# core_io5.net
KiCad netlist of a schematic drawn in EAGLE
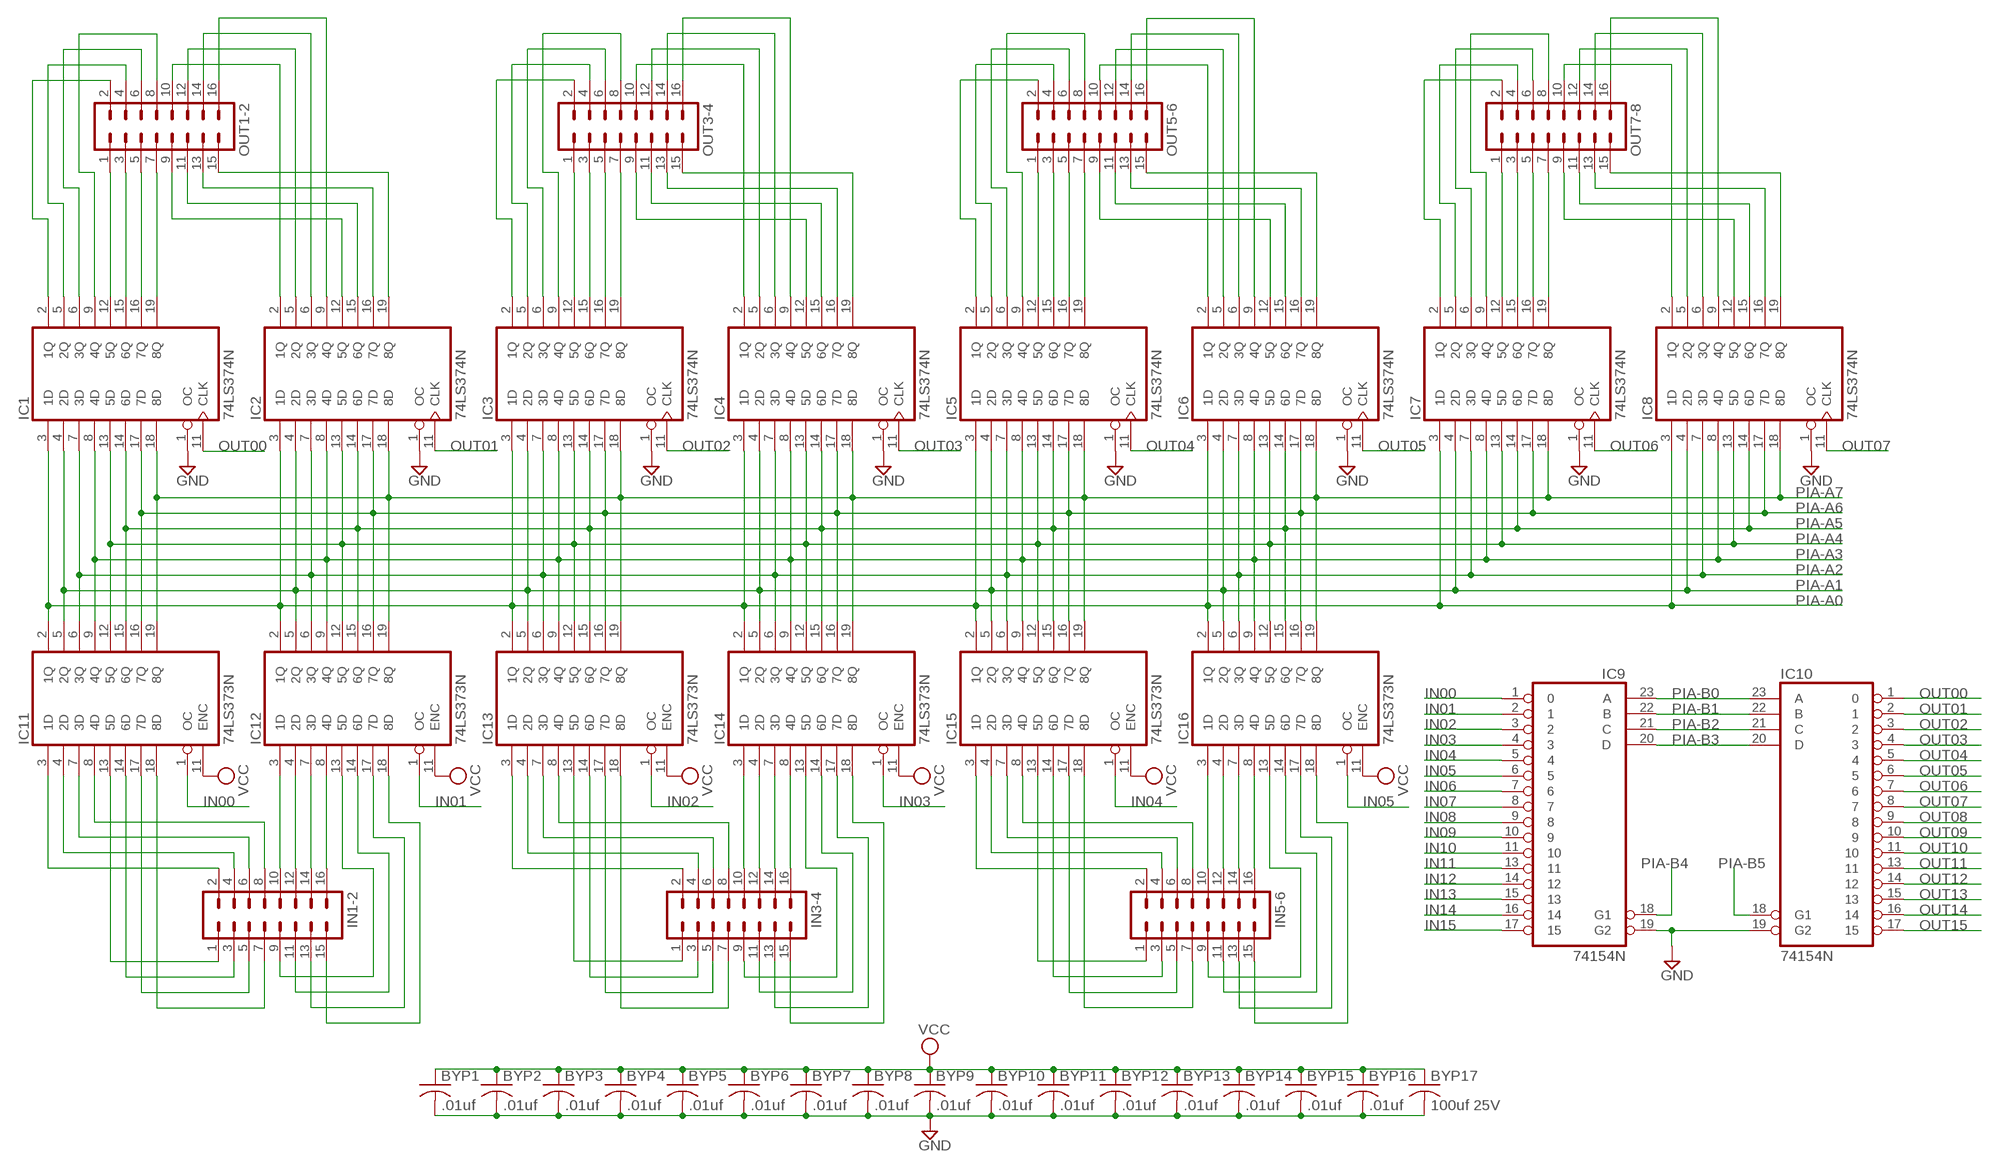
[diagram p0: schematic, sheet 1]
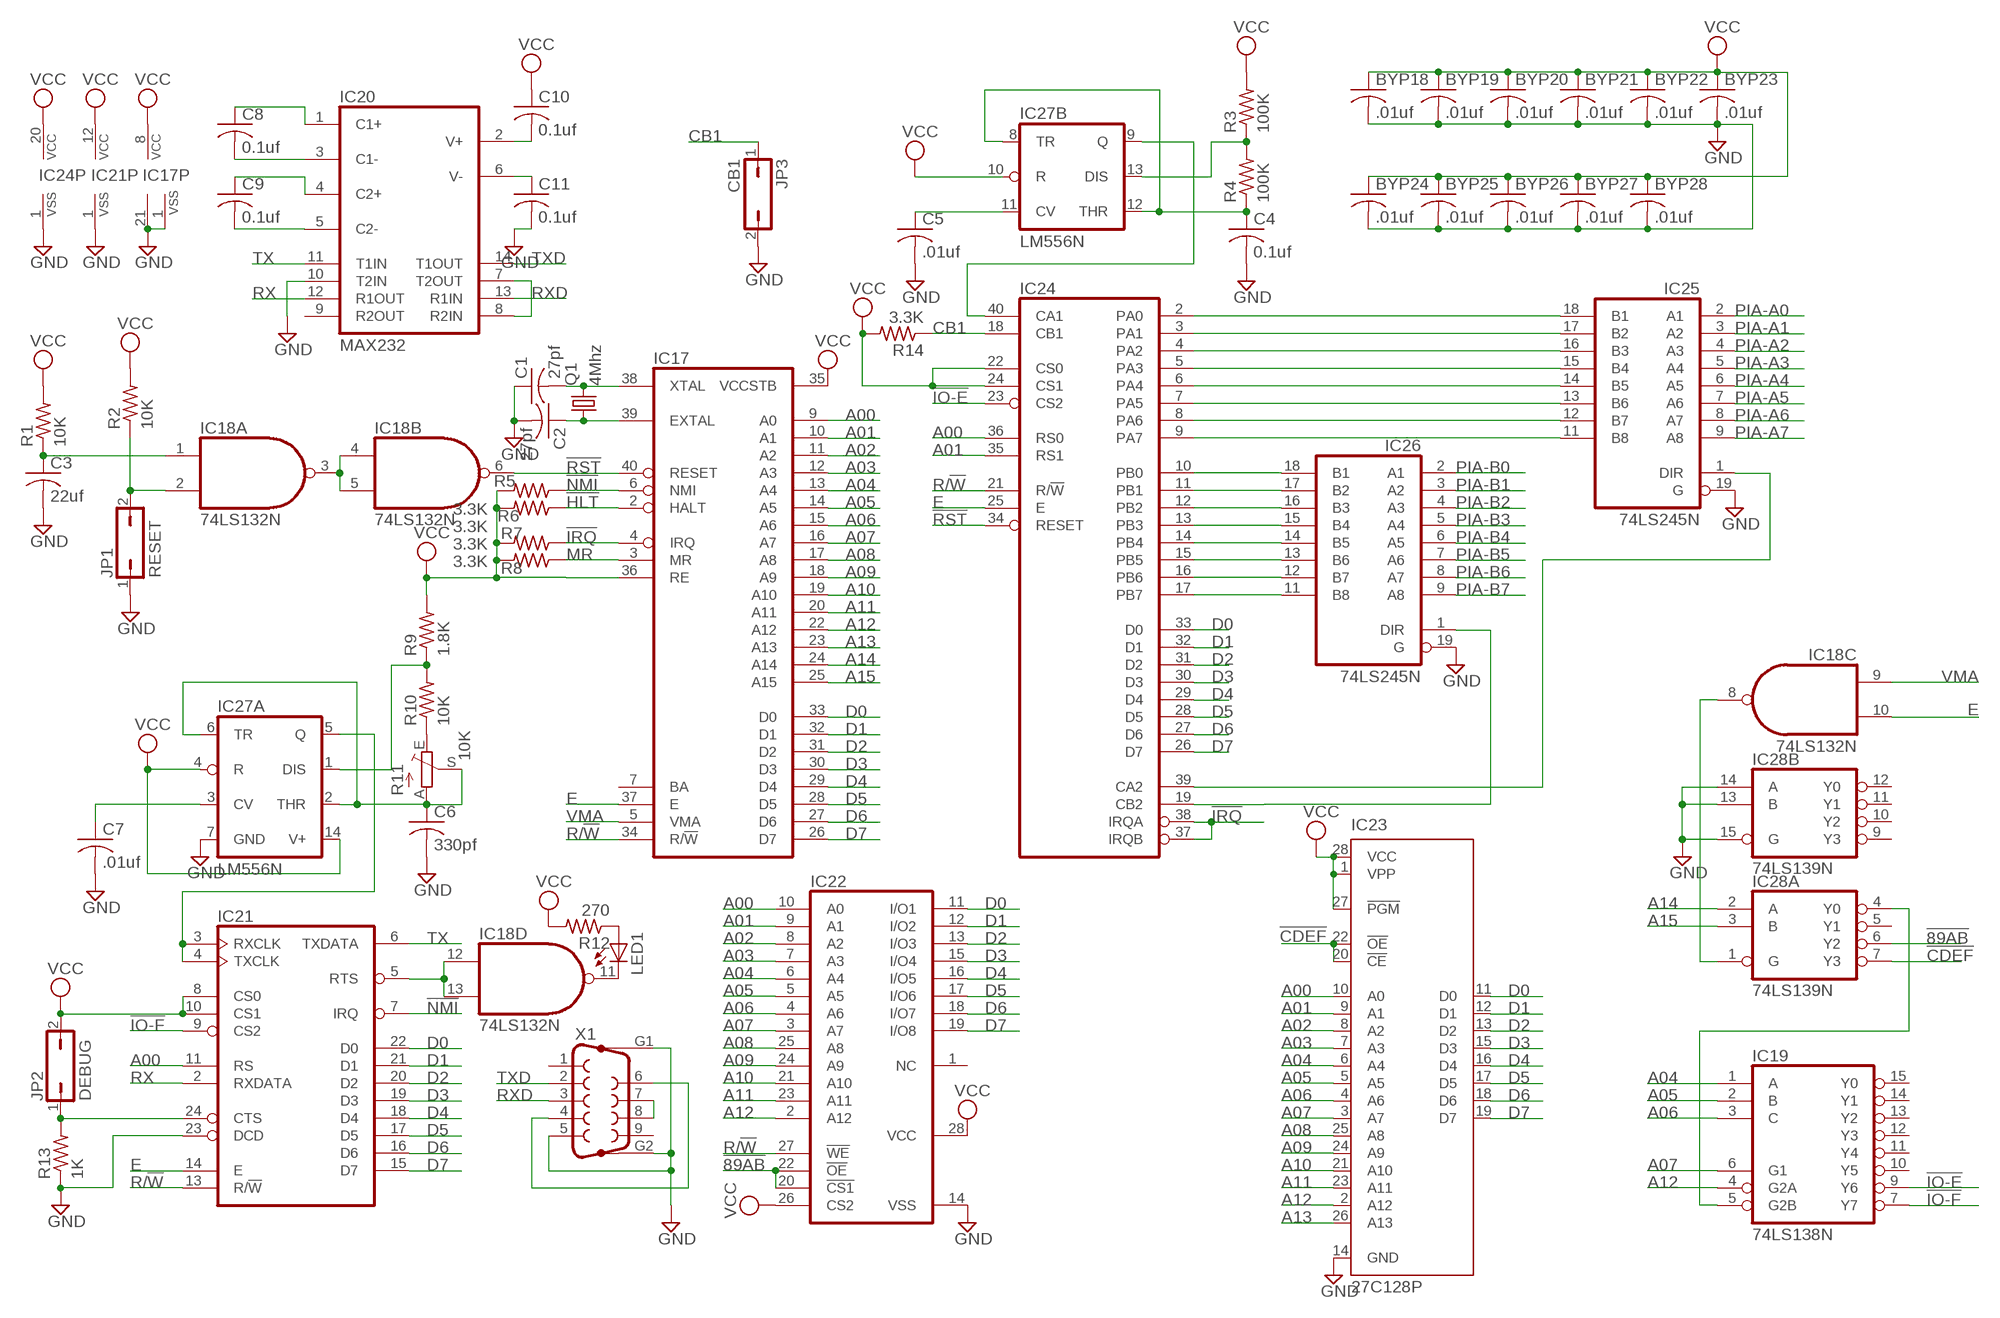
[diagram p1: schematic, sheet 2]
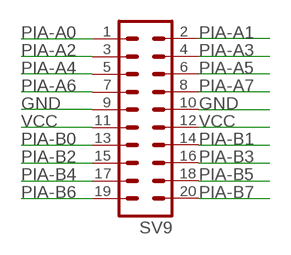
[diagram p2: schematic, sheet 3]

(export (version "E")
  (design (tool "Eeschema 10.0.6"))
  (components
    (comp (ref "BYP1")
      (value ".01uf")
      (footprint "eagle-import:C050-025X075")
      (libsource (lib "eagle-import") (part "C-US050-025X075"))
    )
    (comp (ref "BYP2")
      (value ".01uf")
      (footprint "eagle-import:C050-025X075")
      (libsource (lib "eagle-import") (part "C-US050-025X075"))
    )
    (comp (ref "BYP3")
      (value ".01uf")
      (footprint "eagle-import:C050-025X075")
      (libsource (lib "eagle-import") (part "C-US050-025X075"))
    )
    (comp (ref "BYP4")
      (value ".01uf")
      (footprint "eagle-import:C050-025X075")
      (libsource (lib "eagle-import") (part "C-US050-025X075"))
    )
    (comp (ref "BYP5")
      (value ".01uf")
      (footprint "eagle-import:C050-025X075")
      (libsource (lib "eagle-import") (part "C-US050-025X075"))
    )
    (comp (ref "BYP6")
      (value ".01uf")
      (footprint "eagle-import:C050-025X075")
      (libsource (lib "eagle-import") (part "C-US050-025X075"))
    )
    (comp (ref "BYP7")
      (value ".01uf")
      (footprint "eagle-import:C050-025X075")
      (libsource (lib "eagle-import") (part "C-US050-025X075"))
    )
    (comp (ref "BYP8")
      (value ".01uf")
      (footprint "eagle-import:C050-025X075")
      (libsource (lib "eagle-import") (part "C-US050-025X075"))
    )
    (comp (ref "BYP9")
      (value ".01uf")
      (footprint "eagle-import:C050-025X075")
      (libsource (lib "eagle-import") (part "C-US050-025X075"))
    )
    (comp (ref "BYP10")
      (value ".01uf")
      (footprint "eagle-import:C050-025X075")
      (libsource (lib "eagle-import") (part "C-US050-025X075"))
    )
    (comp (ref "BYP11")
      (value ".01uf")
      (footprint "eagle-import:C050-025X075")
      (libsource (lib "eagle-import") (part "C-US050-025X075"))
    )
    (comp (ref "BYP12")
      (value ".01uf")
      (footprint "eagle-import:C050-025X075")
      (libsource (lib "eagle-import") (part "C-US050-025X075"))
    )
    (comp (ref "BYP13")
      (value ".01uf")
      (footprint "eagle-import:C050-025X075")
      (libsource (lib "eagle-import") (part "C-US050-025X075"))
    )
    (comp (ref "BYP14")
      (value ".01uf")
      (footprint "eagle-import:C050-025X075")
      (libsource (lib "eagle-import") (part "C-US050-025X075"))
    )
    (comp (ref "BYP15")
      (value ".01uf")
      (footprint "eagle-import:C050-025X075")
      (libsource (lib "eagle-import") (part "C-US050-025X075"))
    )
    (comp (ref "BYP16")
      (value ".01uf")
      (footprint "eagle-import:C050-025X075")
      (libsource (lib "eagle-import") (part "C-US050-025X075"))
    )
    (comp (ref "BYP17")
      (value "100uf 25V")
      (footprint "eagle-import:C102-043X133")
      (libsource (lib "eagle-import") (part "C-US102-043X133"))
    )
    (comp (ref "IC1")
      (value "74LS374N")
      (footprint "eagle-import:DIL20")
      (libsource (lib "eagle-import") (part "74374NLS"))
    )
    (comp (ref "IC2")
      (value "74LS374N")
      (footprint "eagle-import:DIL20")
      (libsource (lib "eagle-import") (part "74374NLS"))
    )
    (comp (ref "IC3")
      (value "74LS374N")
      (footprint "eagle-import:DIL20")
      (libsource (lib "eagle-import") (part "74374NLS"))
    )
    (comp (ref "IC4")
      (value "74LS374N")
      (footprint "eagle-import:DIL20")
      (libsource (lib "eagle-import") (part "74374NLS"))
    )
    (comp (ref "IC5")
      (value "74LS374N")
      (footprint "eagle-import:DIL20")
      (libsource (lib "eagle-import") (part "74374NLS"))
    )
    (comp (ref "IC6")
      (value "74LS374N")
      (footprint "eagle-import:DIL20")
      (libsource (lib "eagle-import") (part "74374NLS"))
    )
    (comp (ref "IC7")
      (value "74LS374N")
      (footprint "eagle-import:DIL20")
      (libsource (lib "eagle-import") (part "74374NLS"))
    )
    (comp (ref "IC8")
      (value "74LS374N")
      (footprint "eagle-import:DIL20")
      (libsource (lib "eagle-import") (part "74374NLS"))
    )
    (comp (ref "IC9")
      (value "74154N")
      (footprint "eagle-import:DIL24-6")
      (libsource (lib "eagle-import") (part "74154N"))
    )
    (comp (ref "IC10")
      (value "74154N")
      (footprint "eagle-import:DIL24-6")
      (libsource (lib "eagle-import") (part "74154N"))
    )
    (comp (ref "IC11")
      (value "74LS373N")
      (footprint "eagle-import:DIL20")
      (libsource (lib "eagle-import") (part "74373NLS"))
    )
    (comp (ref "IC12")
      (value "74LS373N")
      (footprint "eagle-import:DIL20")
      (libsource (lib "eagle-import") (part "74373NLS"))
    )
    (comp (ref "IC13")
      (value "74LS373N")
      (footprint "eagle-import:DIL20")
      (libsource (lib "eagle-import") (part "74373NLS"))
    )
    (comp (ref "IC14")
      (value "74LS373N")
      (footprint "eagle-import:DIL20")
      (libsource (lib "eagle-import") (part "74373NLS"))
    )
    (comp (ref "IC15")
      (value "74LS373N")
      (footprint "eagle-import:DIL20")
      (libsource (lib "eagle-import") (part "74373NLS"))
    )
    (comp (ref "IC16")
      (value "74LS373N")
      (footprint "eagle-import:DIL20")
      (libsource (lib "eagle-import") (part "74373NLS"))
    )
    (comp (ref "IN1-2")
      (value "MA08-2")
      (footprint "eagle-import:MA08-2")
      (libsource (lib "eagle-import") (part "MA08-2"))
    )
    (comp (ref "IN3-4")
      (value "MA08-2")
      (footprint "eagle-import:MA08-2")
      (libsource (lib "eagle-import") (part "MA08-2"))
    )
    (comp (ref "IN5-6")
      (value "MA08-2")
      (footprint "eagle-import:MA08-2")
      (libsource (lib "eagle-import") (part "MA08-2"))
    )
    (comp (ref "OUT1-2")
      (value "MA08-2")
      (footprint "eagle-import:MA08-2")
      (libsource (lib "eagle-import") (part "MA08-2"))
    )
    (comp (ref "OUT3-4")
      (value "MA08-2")
      (footprint "eagle-import:MA08-2")
      (libsource (lib "eagle-import") (part "MA08-2"))
    )
    (comp (ref "OUT5-6")
      (value "MA08-2")
      (footprint "eagle-import:MA08-2")
      (libsource (lib "eagle-import") (part "MA08-2"))
    )
    (comp (ref "OUT7-8")
      (value "MA08-2")
      (footprint "eagle-import:MA08-2")
      (libsource (lib "eagle-import") (part "MA08-2"))
    )
    (comp (ref "BYP18")
      (value ".01uf")
      (footprint "eagle-import:C050-025X075")
      (libsource (lib "eagle-import") (part "C-US050-025X075"))
    )
    (comp (ref "BYP19")
      (value ".01uf")
      (footprint "eagle-import:C050-025X075")
      (libsource (lib "eagle-import") (part "C-US050-025X075"))
    )
    (comp (ref "BYP20")
      (value ".01uf")
      (footprint "eagle-import:C050-025X075")
      (libsource (lib "eagle-import") (part "C-US050-025X075"))
    )
    (comp (ref "BYP21")
      (value ".01uf")
      (footprint "eagle-import:C050-025X075")
      (libsource (lib "eagle-import") (part "C-US050-025X075"))
    )
    (comp (ref "BYP22")
      (value ".01uf")
      (footprint "eagle-import:C050-025X075")
      (libsource (lib "eagle-import") (part "C-US050-025X075"))
    )
    (comp (ref "BYP23")
      (value ".01uf")
      (footprint "eagle-import:C050-025X075")
      (libsource (lib "eagle-import") (part "C-US050-025X075"))
    )
    (comp (ref "BYP24")
      (value ".01uf")
      (footprint "eagle-import:C050-025X075")
      (libsource (lib "eagle-import") (part "C-US050-025X075"))
    )
    (comp (ref "BYP25")
      (value ".01uf")
      (footprint "eagle-import:C050-025X075")
      (libsource (lib "eagle-import") (part "C-US050-025X075"))
    )
    (comp (ref "BYP26")
      (value ".01uf")
      (footprint "eagle-import:C050-025X075")
      (libsource (lib "eagle-import") (part "C-US050-025X075"))
    )
    (comp (ref "BYP27")
      (value ".01uf")
      (footprint "eagle-import:C050-025X075")
      (libsource (lib "eagle-import") (part "C-US050-025X075"))
    )
    (comp (ref "BYP28")
      (value ".01uf")
      (footprint "eagle-import:C050-025X075")
      (libsource (lib "eagle-import") (part "C-US050-025X075"))
    )
    (comp (ref "C1")
      (value "27pf")
      (footprint "eagle-import:C050-025X075")
      (libsource (lib "eagle-import") (part "C-US050-025X075"))
    )
    (comp (ref "C2")
      (value "27pf")
      (footprint "eagle-import:C050-025X075")
      (libsource (lib "eagle-import") (part "C-US050-025X075"))
    )
    (comp (ref "C3")
      (value "22uf")
      (footprint "eagle-import:C102-043X133")
      (libsource (lib "eagle-import") (part "C-US102-043X133"))
    )
    (comp (ref "C4")
      (value "0.1uf")
      (footprint "eagle-import:C050-025X075")
      (libsource (lib "eagle-import") (part "C-US050-025X075"))
    )
    (comp (ref "C5")
      (value ".01uf")
      (footprint "eagle-import:C050-025X075")
      (libsource (lib "eagle-import") (part "C-US050-025X075"))
    )
    (comp (ref "C6")
      (value "330pf")
      (footprint "eagle-import:C050-025X075")
      (libsource (lib "eagle-import") (part "C-US050-025X075"))
    )
    (comp (ref "C7")
      (value ".01uf")
      (footprint "eagle-import:C050-025X075")
      (libsource (lib "eagle-import") (part "C-US050-025X075"))
    )
    (comp (ref "C8")
      (value "0.1uf")
      (footprint "eagle-import:C050-025X075")
      (libsource (lib "eagle-import") (part "C-US050-025X075"))
    )
    (comp (ref "C9")
      (value "0.1uf")
      (footprint "eagle-import:C050-025X075")
      (libsource (lib "eagle-import") (part "C-US050-025X075"))
    )
    (comp (ref "C10")
      (value "0.1uf")
      (footprint "eagle-import:C050-025X075")
      (libsource (lib "eagle-import") (part "C-US050-025X075"))
    )
    (comp (ref "C11")
      (value "0.1uf")
      (footprint "eagle-import:C050-025X075")
      (libsource (lib "eagle-import") (part "C-US050-025X075"))
    )
    (comp (ref "IC17")
      (value "6802")
      (footprint "eagle-import:DIL40")
      (libsource (lib "eagle-import") (part "6802"))
    )
    (comp (ref "IC18")
      (value "74LS132N")
      (footprint "eagle-import:DIL14")
      (libsource (lib "eagle-import") (part "7400NLS"))
    )
    (comp (ref "IC19")
      (value "74LS138N")
      (footprint "eagle-import:DIL16")
      (libsource (lib "eagle-import") (part "74138NLS"))
    )
    (comp (ref "IC20")
      (value "MAX232")
      (footprint "eagle-import:DIL16")
      (fields (field (name "MF") "MAXIM") (field (name "MPN") "MAX232ACPE+"))
      (libsource (lib "eagle-import") (part "MAX232"))
    )
    (comp (ref "IC21")
      (value "6850")
      (footprint "eagle-import:DIL24")
      (fields (field (name "MF") "NTE ELECTRONICS") (field (name "MPN") "NTE6850"))
      (libsource (lib "eagle-import") (part "6850"))
    )
    (comp (ref "IC22")
      (value "6264A")
      (footprint "eagle-import:DIL28-6")
      (libsource (lib "eagle-import") (part "6264A"))
    )
    (comp (ref "IC23")
      (value "27C128P")
      (footprint "eagle-import:DIL28-6")
      (libsource (lib "eagle-import") (part "27128PC"))
    )
    (comp (ref "IC24")
      (value "6821")
      (footprint "eagle-import:DIL40")
      (fields (field (name "MF") "NTE ELECTRONICS") (field (name "MPN") "NTE6821"))
      (libsource (lib "eagle-import") (part "6821"))
    )
    (comp (ref "IC25")
      (value "74LS245N")
      (footprint "eagle-import:DIL20")
      (libsource (lib "eagle-import") (part "74245NLS"))
    )
    (comp (ref "IC26")
      (value "74LS245N")
      (footprint "eagle-import:DIL20")
      (libsource (lib "eagle-import") (part "74245NLS"))
    )
    (comp (ref "IC27")
      (value "LM556N")
      (footprint "eagle-import:DIL14")
      (libsource (lib "eagle-import") (part "556NLM"))
    )
    (comp (ref "IC28")
      (value "74LS139N")
      (footprint "eagle-import:DIL16")
      (libsource (lib "eagle-import") (part "74139NLS"))
    )
    (comp (ref "JP1")
      (value "RESET")
      (footprint "eagle-import:JP1")
      (libsource (lib "eagle-import") (part "JP1Q"))
    )
    (comp (ref "JP2")
      (value "DEBUG")
      (footprint "eagle-import:JP1")
      (libsource (lib "eagle-import") (part "JP1Q"))
    )
    (comp (ref "JP3")
      (value "CB1")
      (footprint "eagle-import:JP1")
      (libsource (lib "eagle-import") (part "JP1Q"))
    )
    (comp (ref "LED1")
      (value "LED3MM")
      (footprint "eagle-import:LED3MM")
      (libsource (lib "eagle-import") (part "LED3MM"))
    )
    (comp (ref "Q1")
      (value "4Mhz")
      (footprint "eagle-import:HC18U-V")
      (libsource (lib "eagle-import") (part "CRYSTALHC18U-V"))
    )
    (comp (ref "R1")
      (value "10K")
      (footprint "eagle-import:0207_7")
      (libsource (lib "eagle-import") (part "R-US_0207/7"))
    )
    (comp (ref "R2")
      (value "10K")
      (footprint "eagle-import:0207_7")
      (libsource (lib "eagle-import") (part "R-US_0207/7"))
    )
    (comp (ref "R3")
      (value "100K")
      (footprint "eagle-import:0207_7")
      (libsource (lib "eagle-import") (part "R-US_0207/7"))
    )
    (comp (ref "R4")
      (value "100K")
      (footprint "eagle-import:0207_7")
      (libsource (lib "eagle-import") (part "R-US_0207/7"))
    )
    (comp (ref "R5")
      (value "3.3K")
      (footprint "eagle-import:0207_7")
      (libsource (lib "eagle-import") (part "R-US_0207/7"))
    )
    (comp (ref "R6")
      (value "3.3K")
      (footprint "eagle-import:0207_7")
      (libsource (lib "eagle-import") (part "R-US_0207/7"))
    )
    (comp (ref "R7")
      (value "3.3K")
      (footprint "eagle-import:0207_7")
      (libsource (lib "eagle-import") (part "R-US_0207/7"))
    )
    (comp (ref "R8")
      (value "3.3K")
      (footprint "eagle-import:0207_7")
      (libsource (lib "eagle-import") (part "R-US_0207/7"))
    )
    (comp (ref "R9")
      (value "1.8K")
      (footprint "eagle-import:0207_7")
      (libsource (lib "eagle-import") (part "R-US_0207/7"))
    )
    (comp (ref "R10")
      (value "10K")
      (footprint "eagle-import:0207_7")
      (libsource (lib "eagle-import") (part "R-US_0207/7"))
    )
    (comp (ref "R11")
      (value "10K")
      (footprint "eagle-import:SP19L")
      (libsource (lib "eagle-import") (part "TRIM_EU-B90P"))
    )
    (comp (ref "R12")
      (value "270")
      (footprint "eagle-import:0207_7")
      (libsource (lib "eagle-import") (part "R-US_0207/7"))
    )
    (comp (ref "R13")
      (value "1K")
      (footprint "eagle-import:0207_7")
      (libsource (lib "eagle-import") (part "R-US_0207/7"))
    )
    (comp (ref "R14")
      (value "3.3K")
      (footprint "eagle-import:0207_7")
      (libsource (lib "eagle-import") (part "R-US_0207/7"))
    )
    (comp (ref "X1")
      (value "F09HP")
      (footprint "eagle-import:F09HP")
      (libsource (lib "eagle-import") (part "F09HP"))
    )
    (comp (ref "SV9")
      (value "MA10-2")
      (footprint "eagle-import:MA10-2")
      (libsource (lib "eagle-import") (part "MA10-2"))
    )
  )
  (nets
    (net (code "1") (name "A00") (class "Default")
      (node (ref "IC17") (pin "9") (pinfunction "A0_9") (pintype "output"))
      (node (ref "IC21") (pin "11") (pinfunction "RS_11") (pintype "input"))
      (node (ref "IC22") (pin "10") (pinfunction "A0_10") (pintype "input"))
      (node (ref "IC23") (pin "10") (pinfunction "A0_10") (pintype "input"))
      (node (ref "IC24") (pin "36") (pinfunction "RS0_36") (pintype "input"))
    )
    (net (code "2") (name "A01") (class "Default")
      (node (ref "IC17") (pin "10") (pinfunction "A1_10") (pintype "output"))
      (node (ref "IC22") (pin "9") (pinfunction "A1_9") (pintype "input"))
      (node (ref "IC23") (pin "9") (pinfunction "A1_9") (pintype "input"))
      (node (ref "IC24") (pin "35") (pinfunction "RS1_35") (pintype "input"))
    )
    (net (code "3") (name "A02") (class "Default")
      (node (ref "IC17") (pin "11") (pinfunction "A2_11") (pintype "output"))
      (node (ref "IC22") (pin "8") (pinfunction "A2_8") (pintype "input"))
      (node (ref "IC23") (pin "8") (pinfunction "A2_8") (pintype "input"))
    )
    (net (code "4") (name "A03") (class "Default")
      (node (ref "IC17") (pin "12") (pinfunction "A3_12") (pintype "output"))
      (node (ref "IC22") (pin "7") (pinfunction "A3_7") (pintype "input"))
      (node (ref "IC23") (pin "7") (pinfunction "A3_7") (pintype "input"))
    )
    (net (code "5") (name "A04") (class "Default")
      (node (ref "IC17") (pin "13") (pinfunction "A4_13") (pintype "output"))
      (node (ref "IC19") (pin "1") (pinfunction "A_1") (pintype "input"))
      (node (ref "IC22") (pin "6") (pinfunction "A4_6") (pintype "input"))
      (node (ref "IC23") (pin "6") (pinfunction "A4_6") (pintype "input"))
    )
    (net (code "6") (name "A05") (class "Default")
      (node (ref "IC17") (pin "14") (pinfunction "A5_14") (pintype "output"))
      (node (ref "IC19") (pin "2") (pinfunction "B_2") (pintype "input"))
      (node (ref "IC22") (pin "5") (pinfunction "A5_5") (pintype "input"))
      (node (ref "IC23") (pin "5") (pinfunction "A5_5") (pintype "input"))
    )
    (net (code "7") (name "A06") (class "Default")
      (node (ref "IC17") (pin "15") (pinfunction "A6_15") (pintype "output"))
      (node (ref "IC19") (pin "3") (pinfunction "C_3") (pintype "input"))
      (node (ref "IC22") (pin "4") (pinfunction "A6_4") (pintype "input"))
      (node (ref "IC23") (pin "4") (pinfunction "A6_4") (pintype "input"))
    )
    (net (code "8") (name "A07") (class "Default")
      (node (ref "IC17") (pin "16") (pinfunction "A7_16") (pintype "output"))
      (node (ref "IC19") (pin "6") (pinfunction "G1_6") (pintype "input"))
      (node (ref "IC22") (pin "3") (pinfunction "A7_3") (pintype "input"))
      (node (ref "IC23") (pin "3") (pinfunction "A7_3") (pintype "input"))
    )
    (net (code "9") (name "A08") (class "Default")
      (node (ref "IC17") (pin "17") (pinfunction "A8_17") (pintype "output"))
      (node (ref "IC22") (pin "25") (pinfunction "A8_25") (pintype "input"))
      (node (ref "IC23") (pin "25") (pinfunction "A8_25") (pintype "input"))
    )
    (net (code "10") (name "A09") (class "Default")
      (node (ref "IC17") (pin "18") (pinfunction "A9_18") (pintype "output"))
      (node (ref "IC22") (pin "24") (pinfunction "A9_24") (pintype "input"))
      (node (ref "IC23") (pin "24") (pinfunction "A9_24") (pintype "input"))
    )
    (net (code "11") (name "A10") (class "Default")
      (node (ref "IC17") (pin "19") (pinfunction "A10_19") (pintype "output"))
      (node (ref "IC22") (pin "21") (pinfunction "A10_21") (pintype "input"))
      (node (ref "IC23") (pin "21") (pinfunction "A10_21") (pintype "input"))
    )
    (net (code "12") (name "A11") (class "Default")
      (node (ref "IC17") (pin "20") (pinfunction "A11_20") (pintype "output"))
      (node (ref "IC22") (pin "23") (pinfunction "A11_23") (pintype "input"))
      (node (ref "IC23") (pin "23") (pinfunction "A11_23") (pintype "input"))
    )
    (net (code "13") (name "A12") (class "Default")
      (node (ref "IC17") (pin "22") (pinfunction "A12_22") (pintype "output"))
      (node (ref "IC19") (pin "4") (pinfunction "G2A_4") (pintype "input"))
      (node (ref "IC22") (pin "2") (pinfunction "A12_2") (pintype "input"))
      (node (ref "IC23") (pin "2") (pinfunction "A12_2") (pintype "input"))
    )
    (net (code "14") (name "A13") (class "Default")
      (node (ref "IC17") (pin "23") (pinfunction "A13_23") (pintype "output"))
      (node (ref "IC23") (pin "26") (pinfunction "A13_26") (pintype "input"))
    )
    (net (code "15") (name "A14") (class "Default")
      (node (ref "IC17") (pin "24") (pinfunction "A14_24") (pintype "output"))
      (node (ref "IC28") (pin "2") (pinfunction "A_2") (pintype "input"))
    )
    (net (code "16") (name "A15") (class "Default")
      (node (ref "IC17") (pin "25") (pinfunction "A15_25") (pintype "output"))
      (node (ref "IC28") (pin "3") (pinfunction "B_3") (pintype "input"))
    )
    (net (code "17") (name "CB1") (class "Default")
      (node (ref "IC24") (pin "18") (pinfunction "CB1_18") (pintype "input"))
      (node (ref "JP3") (pin "1") (pinfunction "1_1") (pintype "passive"))
      (node (ref "R14") (pin "1") (pinfunction "1_1") (pintype "passive"))
    )
    (net (code "18") (name "D0") (class "Default")
      (node (ref "IC17") (pin "33") (pinfunction "D0_33") (pintype "bidirectional"))
      (node (ref "IC21") (pin "22") (pinfunction "D0_22") (pintype "bidirectional"))
      (node (ref "IC22") (pin "11") (pinfunction "I/O1_11") (pintype "bidirectional"))
      (node (ref "IC23") (pin "11") (pinfunction "D0_11") (pintype "tri_state"))
      (node (ref "IC24") (pin "33") (pinfunction "D0_33") (pintype "bidirectional"))
    )
    (net (code "19") (name "D1") (class "Default")
      (node (ref "IC17") (pin "32") (pinfunction "D1_32") (pintype "bidirectional"))
      (node (ref "IC21") (pin "21") (pinfunction "D1_21") (pintype "bidirectional"))
      (node (ref "IC22") (pin "12") (pinfunction "I/O2_12") (pintype "bidirectional"))
      (node (ref "IC23") (pin "12") (pinfunction "D1_12") (pintype "tri_state"))
      (node (ref "IC24") (pin "32") (pinfunction "D1_32") (pintype "bidirectional"))
    )
    (net (code "20") (name "D2") (class "Default")
      (node (ref "IC17") (pin "31") (pinfunction "D2_31") (pintype "bidirectional"))
      (node (ref "IC21") (pin "20") (pinfunction "D2_20") (pintype "bidirectional"))
      (node (ref "IC22") (pin "13") (pinfunction "I/O3_13") (pintype "bidirectional"))
      (node (ref "IC23") (pin "13") (pinfunction "D2_13") (pintype "tri_state"))
      (node (ref "IC24") (pin "31") (pinfunction "D2_31") (pintype "bidirectional"))
    )
    (net (code "21") (name "D3") (class "Default")
      (node (ref "IC17") (pin "30") (pinfunction "D3_30") (pintype "bidirectional"))
      (node (ref "IC21") (pin "19") (pinfunction "D3_19") (pintype "bidirectional"))
      (node (ref "IC22") (pin "15") (pinfunction "I/O4_15") (pintype "bidirectional"))
      (node (ref "IC23") (pin "15") (pinfunction "D3_15") (pintype "tri_state"))
      (node (ref "IC24") (pin "30") (pinfunction "D3_30") (pintype "bidirectional"))
    )
    (net (code "22") (name "D4") (class "Default")
      (node (ref "IC17") (pin "29") (pinfunction "D4_29") (pintype "bidirectional"))
      (node (ref "IC21") (pin "18") (pinfunction "D4_18") (pintype "bidirectional"))
      (node (ref "IC22") (pin "16") (pinfunction "I/O5_16") (pintype "bidirectional"))
      (node (ref "IC23") (pin "16") (pinfunction "D4_16") (pintype "tri_state"))
      (node (ref "IC24") (pin "29") (pinfunction "D4_29") (pintype "bidirectional"))
    )
    (net (code "23") (name "D5") (class "Default")
      (node (ref "IC17") (pin "28") (pinfunction "D5_28") (pintype "bidirectional"))
      (node (ref "IC21") (pin "17") (pinfunction "D5_17") (pintype "bidirectional"))
      (node (ref "IC22") (pin "17") (pinfunction "I/O6_17") (pintype "bidirectional"))
      (node (ref "IC23") (pin "17") (pinfunction "D5_17") (pintype "tri_state"))
      (node (ref "IC24") (pin "28") (pinfunction "D5_28") (pintype "bidirectional"))
    )
    (net (code "24") (name "D6") (class "Default")
      (node (ref "IC17") (pin "27") (pinfunction "D6_27") (pintype "bidirectional"))
      (node (ref "IC21") (pin "16") (pinfunction "D6_16") (pintype "bidirectional"))
      (node (ref "IC22") (pin "18") (pinfunction "I/O7_18") (pintype "bidirectional"))
      (node (ref "IC23") (pin "18") (pinfunction "D6_18") (pintype "tri_state"))
      (node (ref "IC24") (pin "27") (pinfunction "D6_27") (pintype "bidirectional"))
    )
    (net (code "25") (name "D7") (class "Default")
      (node (ref "IC17") (pin "26") (pinfunction "D7_26") (pintype "bidirectional"))
      (node (ref "IC21") (pin "15") (pinfunction "D7_15") (pintype "bidirectional"))
      (node (ref "IC22") (pin "19") (pinfunction "I/O8_19") (pintype "bidirectional"))
      (node (ref "IC23") (pin "19") (pinfunction "D7_19") (pintype "tri_state"))
      (node (ref "IC24") (pin "26") (pinfunction "D7_26") (pintype "bidirectional"))
    )
    (net (code "26") (name "E") (class "Default")
      (node (ref "IC17") (pin "37") (pinfunction "E_37") (pintype "output"))
      (node (ref "IC18") (pin "10") (pinfunction "I1_10") (pintype "input"))
      (node (ref "IC21") (pin "14") (pinfunction "E_14") (pintype "input"))
      (node (ref "IC24") (pin "25") (pinfunction "E_25") (pintype "input"))
    )
    (net (code "27") (name "GND") (class "Default")
      (node (ref "BYP1") (pin "2") (pinfunction "2_2") (pintype "passive"))
      (node (ref "BYP10") (pin "2") (pinfunction "2_2") (pintype "passive"))
      (node (ref "BYP11") (pin "2") (pinfunction "2_2") (pintype "passive"))
      (node (ref "BYP12") (pin "2") (pinfunction "2_2") (pintype "passive"))
      (node (ref "BYP13") (pin "2") (pinfunction "2_2") (pintype "passive"))
      (node (ref "BYP14") (pin "2") (pinfunction "2_2") (pintype "passive"))
      (node (ref "BYP15") (pin "2") (pinfunction "2_2") (pintype "passive"))
      (node (ref "BYP16") (pin "2") (pinfunction "2_2") (pintype "passive"))
      (node (ref "BYP17") (pin "2") (pinfunction "2_2") (pintype "passive"))
      (node (ref "BYP18") (pin "2") (pinfunction "2_2") (pintype "passive"))
      (node (ref "BYP19") (pin "2") (pinfunction "2_2") (pintype "passive"))
      (node (ref "BYP2") (pin "2") (pinfunction "2_2") (pintype "passive"))
      (node (ref "BYP20") (pin "2") (pinfunction "2_2") (pintype "passive"))
      (node (ref "BYP21") (pin "2") (pinfunction "2_2") (pintype "passive"))
      (node (ref "BYP22") (pin "2") (pinfunction "2_2") (pintype "passive"))
      (node (ref "BYP23") (pin "2") (pinfunction "2_2") (pintype "passive"))
      (node (ref "BYP24") (pin "2") (pinfunction "2_2") (pintype "passive"))
      (node (ref "BYP25") (pin "2") (pinfunction "2_2") (pintype "passive"))
      (node (ref "BYP26") (pin "2") (pinfunction "2_2") (pintype "passive"))
      (node (ref "BYP27") (pin "2") (pinfunction "2_2") (pintype "passive"))
      (node (ref "BYP28") (pin "2") (pinfunction "2_2") (pintype "passive"))
      (node (ref "BYP3") (pin "2") (pinfunction "2_2") (pintype "passive"))
      (node (ref "BYP4") (pin "2") (pinfunction "2_2") (pintype "passive"))
      (node (ref "BYP5") (pin "2") (pinfunction "2_2") (pintype "passive"))
      (node (ref "BYP6") (pin "2") (pinfunction "2_2") (pintype "passive"))
      (node (ref "BYP7") (pin "2") (pinfunction "2_2") (pintype "passive"))
      (node (ref "BYP8") (pin "2") (pinfunction "2_2") (pintype "passive"))
      (node (ref "BYP9") (pin "2") (pinfunction "2_2") (pintype "passive"))
      (node (ref "C1") (pin "1") (pinfunction "1_1") (pintype "passive"))
      (node (ref "C11") (pin "2") (pinfunction "2_2") (pintype "passive"))
      (node (ref "C2") (pin "2") (pinfunction "2_2") (pintype "passive"))
      (node (ref "C3") (pin "2") (pinfunction "2_2") (pintype "passive"))
      (node (ref "C4") (pin "2") (pinfunction "2_2") (pintype "passive"))
      (node (ref "C5") (pin "2") (pinfunction "2_2") (pintype "passive"))
      (node (ref "C6") (pin "2") (pinfunction "2_2") (pintype "passive"))
      (node (ref "C7") (pin "2") (pinfunction "2_2") (pintype "passive"))
      (node (ref "IC1") (pin "1") (pinfunction "OC_1") (pintype "input"))
      (node (ref "IC10") (pin "19") (pinfunction "G2_19") (pintype "input"))
      (node (ref "IC17") (pin "1") (pinfunction "VSS_1") (pintype "power_in"))
      (node (ref "IC17") (pin "21") (pinfunction "VSS_21") (pintype "power_in"))
      (node (ref "IC2") (pin "1") (pinfunction "OC_1") (pintype "input"))
      (node (ref "IC20") (pin "10") (pinfunction "T2IN_10") (pintype "input"))
      (node (ref "IC21") (pin "1") (pinfunction "VSS_1") (pintype "power_in"))
      (node (ref "IC21") (pin "23") (pinfunction "DCD_23") (pintype "input"))
      (node (ref "IC22") (pin "14") (pinfunction "VSS_14") (pintype "power_in"))
      (node (ref "IC23") (pin "14") (pinfunction "GND_14") (pintype "power_in"))
      (node (ref "IC24") (pin "1") (pinfunction "VSS_1") (pintype "power_in"))
      (node (ref "IC25") (pin "19") (pinfunction "G_19") (pintype "input"))
      (node (ref "IC26") (pin "19") (pinfunction "G_19") (pintype "input"))
      (node (ref "IC27") (pin "7") (pinfunction "GND_7") (pintype "power_in"))
      (node (ref "IC28") (pin "13") (pinfunction "B_13") (pintype "input"))
      (node (ref "IC28") (pin "14") (pinfunction "A_14") (pintype "input"))
      (node (ref "IC28") (pin "15") (pinfunction "G_15") (pintype "input"))
      (node (ref "IC3") (pin "1") (pinfunction "OC_1") (pintype "input"))
      (node (ref "IC4") (pin "1") (pinfunction "OC_1") (pintype "input"))
      (node (ref "IC5") (pin "1") (pinfunction "OC_1") (pintype "input"))
      (node (ref "IC6") (pin "1") (pinfunction "OC_1") (pintype "input"))
      (node (ref "IC7") (pin "1") (pinfunction "OC_1") (pintype "input"))
      (node (ref "IC8") (pin "1") (pinfunction "OC_1") (pintype "input"))
      (node (ref "IC9") (pin "19") (pinfunction "G2_19") (pintype "input"))
      (node (ref "JP1") (pin "1") (pinfunction "1_1") (pintype "passive"))
      (node (ref "JP3") (pin "2") (pinfunction "2_2") (pintype "passive"))
      (node (ref "R13") (pin "1") (pinfunction "1_1") (pintype "passive"))
      (node (ref "SV9") (pin "10") (pinfunction "10_10") (pintype "passive"))
      (node (ref "SV9") (pin "9") (pinfunction "9_9") (pintype "passive"))
      (node (ref "X1") (pin "5") (pinfunction "5_5") (pintype "passive"))
      (node (ref "X1") (pin "G1") (pinfunction "G1_G1") (pintype "passive"))
      (node (ref "X1") (pin "G2") (pinfunction "G2_G2") (pintype "passive"))
    )
    (net (code "28") (name "IN00") (class "Default")
      (node (ref "IC11") (pin "1") (pinfunction "OC_1") (pintype "input"))
      (node (ref "IC9") (pin "1") (pinfunction "0_1") (pintype "output"))
    )
    (net (code "29") (name "IN01") (class "Default")
      (node (ref "IC12") (pin "1") (pinfunction "OC_1") (pintype "input"))
      (node (ref "IC9") (pin "2") (pinfunction "1_2") (pintype "output"))
    )
    (net (code "30") (name "IN02") (class "Default")
      (node (ref "IC13") (pin "1") (pinfunction "OC_1") (pintype "input"))
      (node (ref "IC9") (pin "3") (pinfunction "2_3") (pintype "output"))
    )
    (net (code "31") (name "IN03") (class "Default")
      (node (ref "IC14") (pin "1") (pinfunction "OC_1") (pintype "input"))
      (node (ref "IC9") (pin "4") (pinfunction "3_4") (pintype "output"))
    )
    (net (code "32") (name "IN04") (class "Default")
      (node (ref "IC15") (pin "1") (pinfunction "OC_1") (pintype "input"))
      (node (ref "IC9") (pin "5") (pinfunction "4_5") (pintype "output"))
    )
    (net (code "33") (name "IN05") (class "Default")
      (node (ref "IC16") (pin "1") (pinfunction "OC_1") (pintype "input"))
      (node (ref "IC9") (pin "6") (pinfunction "5_6") (pintype "output"))
    )
    (net (code "34") (name "IN06") (class "Default")
      (node (ref "IC9") (pin "7") (pinfunction "6_7") (pintype "output"))
    )
    (net (code "35") (name "IN07") (class "Default")
      (node (ref "IC9") (pin "8") (pinfunction "7_8") (pintype "output"))
    )
    (net (code "36") (name "IN08") (class "Default")
      (node (ref "IC9") (pin "9") (pinfunction "8_9") (pintype "output"))
    )
    (net (code "37") (name "IN09") (class "Default")
      (node (ref "IC9") (pin "10") (pinfunction "9_10") (pintype "output"))
    )
    (net (code "38") (name "IN10") (class "Default")
      (node (ref "IC9") (pin "11") (pinfunction "10_11") (pintype "output"))
    )
    (net (code "39") (name "IN11") (class "Default")
      (node (ref "IC9") (pin "13") (pinfunction "11_13") (pintype "output"))
    )
    (net (code "40") (name "IN12") (class "Default")
      (node (ref "IC9") (pin "14") (pinfunction "12_14") (pintype "output"))
    )
    (net (code "41") (name "IN13") (class "Default")
      (node (ref "IC9") (pin "15") (pinfunction "13_15") (pintype "output"))
    )
    (net (code "42") (name "IN14") (class "Default")
      (node (ref "IC9") (pin "16") (pinfunction "14_16") (pintype "output"))
    )
    (net (code "43") (name "IN15") (class "Default")
      (node (ref "IC9") (pin "17") (pinfunction "15_17") (pintype "output"))
    )
    (net (code "44") (name "MR") (class "Default")
      (node (ref "IC17") (pin "3") (pinfunction "MR_3") (pintype "input"))
      (node (ref "R8") (pin "1") (pinfunction "1_1") (pintype "passive"))
    )
    (net (code "45") (name "Net-(IC1A-1Q)") (class "Default")
      (node (ref "IC1") (pin "2") (pinfunction "1Q_2") (pintype "tri_state"))
      (node (ref "OUT1-2") (pin "2") (pinfunction "2_2") (pintype "passive"))
    )
    (net (code "46") (name "Net-(IC1A-2Q)") (class "Default")
      (node (ref "IC1") (pin "5") (pinfunction "2Q_5") (pintype "tri_state"))
      (node (ref "OUT1-2") (pin "4") (pinfunction "4_4") (pintype "passive"))
    )
    (net (code "47") (name "Net-(IC1A-3Q)") (class "Default")
      (node (ref "IC1") (pin "6") (pinfunction "3Q_6") (pintype "tri_state"))
      (node (ref "OUT1-2") (pin "6") (pinfunction "6_6") (pintype "passive"))
    )
    (net (code "48") (name "Net-(IC1A-4Q)") (class "Default")
      (node (ref "IC1") (pin "9") (pinfunction "4Q_9") (pintype "tri_state"))
      (node (ref "OUT1-2") (pin "8") (pinfunction "8_8") (pintype "passive"))
    )
    (net (code "49") (name "Net-(IC1A-5Q)") (class "Default")
      (node (ref "IC1") (pin "12") (pinfunction "5Q_12") (pintype "tri_state"))
      (node (ref "OUT1-2") (pin "1") (pinfunction "1_1") (pintype "passive"))
    )
    (net (code "50") (name "Net-(IC1A-6Q)") (class "Default")
      (node (ref "IC1") (pin "15") (pinfunction "6Q_15") (pintype "tri_state"))
      (node (ref "OUT1-2") (pin "3") (pinfunction "3_3") (pintype "passive"))
    )
    (net (code "51") (name "Net-(IC1A-7Q)") (class "Default")
      (node (ref "IC1") (pin "16") (pinfunction "7Q_16") (pintype "tri_state"))
      (node (ref "OUT1-2") (pin "5") (pinfunction "5_5") (pintype "passive"))
    )
    (net (code "52") (name "Net-(IC1A-8Q)") (class "Default")
      (node (ref "IC1") (pin "19") (pinfunction "8Q_19") (pintype "tri_state"))
      (node (ref "OUT1-2") (pin "7") (pinfunction "7_7") (pintype "passive"))
    )
    (net (code "53") (name "Net-(IC2A-1Q)") (class "Default")
      (node (ref "IC2") (pin "2") (pinfunction "1Q_2") (pintype "tri_state"))
      (node (ref "OUT1-2") (pin "10") (pinfunction "10_10") (pintype "passive"))
    )
    (net (code "54") (name "Net-(IC2A-2Q)") (class "Default")
      (node (ref "IC2") (pin "5") (pinfunction "2Q_5") (pintype "tri_state"))
      (node (ref "OUT1-2") (pin "12") (pinfunction "12_12") (pintype "passive"))
    )
    (net (code "55") (name "Net-(IC2A-3Q)") (class "Default")
      (node (ref "IC2") (pin "6") (pinfunction "3Q_6") (pintype "tri_state"))
      (node (ref "OUT1-2") (pin "14") (pinfunction "14_14") (pintype "passive"))
    )
    (net (code "56") (name "Net-(IC2A-4Q)") (class "Default")
      (node (ref "IC2") (pin "9") (pinfunction "4Q_9") (pintype "tri_state"))
      (node (ref "OUT1-2") (pin "16") (pinfunction "16_16") (pintype "passive"))
    )
    (net (code "57") (name "Net-(IC2A-5Q)") (class "Default")
      (node (ref "IC2") (pin "12") (pinfunction "5Q_12") (pintype "tri_state"))
      (node (ref "OUT1-2") (pin "9") (pinfunction "9_9") (pintype "passive"))
    )
    (net (code "58") (name "Net-(IC2A-6Q)") (class "Default")
      (node (ref "IC2") (pin "15") (pinfunction "6Q_15") (pintype "tri_state"))
      (node (ref "OUT1-2") (pin "11") (pinfunction "11_11") (pintype "passive"))
    )
    (net (code "59") (name "Net-(IC2A-7Q)") (class "Default")
      (node (ref "IC2") (pin "16") (pinfunction "7Q_16") (pintype "tri_state"))
      (node (ref "OUT1-2") (pin "13") (pinfunction "13_13") (pintype "passive"))
    )
    (net (code "60") (name "Net-(IC2A-8Q)") (class "Default")
      (node (ref "IC2") (pin "19") (pinfunction "8Q_19") (pintype "tri_state"))
      (node (ref "OUT1-2") (pin "15") (pinfunction "15_15") (pintype "passive"))
    )
    (net (code "61") (name "Net-(IC3A-1Q)") (class "Default")
      (node (ref "IC3") (pin "2") (pinfunction "1Q_2") (pintype "tri_state"))
      (node (ref "OUT3-4") (pin "2") (pinfunction "2_2") (pintype "passive"))
    )
    (net (code "62") (name "Net-(IC3A-2Q)") (class "Default")
      (node (ref "IC3") (pin "5") (pinfunction "2Q_5") (pintype "tri_state"))
      (node (ref "OUT3-4") (pin "4") (pinfunction "4_4") (pintype "passive"))
    )
    (net (code "63") (name "Net-(IC3A-3Q)") (class "Default")
      (node (ref "IC3") (pin "6") (pinfunction "3Q_6") (pintype "tri_state"))
      (node (ref "OUT3-4") (pin "6") (pinfunction "6_6") (pintype "passive"))
    )
    (net (code "64") (name "Net-(IC3A-4Q)") (class "Default")
      (node (ref "IC3") (pin "9") (pinfunction "4Q_9") (pintype "tri_state"))
      (node (ref "OUT3-4") (pin "8") (pinfunction "8_8") (pintype "passive"))
    )
    (net (code "65") (name "Net-(IC3A-5Q)") (class "Default")
      (node (ref "IC3") (pin "12") (pinfunction "5Q_12") (pintype "tri_state"))
      (node (ref "OUT3-4") (pin "1") (pinfunction "1_1") (pintype "passive"))
    )
    (net (code "66") (name "Net-(IC3A-6Q)") (class "Default")
      (node (ref "IC3") (pin "15") (pinfunction "6Q_15") (pintype "tri_state"))
      (node (ref "OUT3-4") (pin "3") (pinfunction "3_3") (pintype "passive"))
    )
    (net (code "67") (name "Net-(IC3A-7Q)") (class "Default")
      (node (ref "IC3") (pin "16") (pinfunction "7Q_16") (pintype "tri_state"))
      (node (ref "OUT3-4") (pin "5") (pinfunction "5_5") (pintype "passive"))
    )
    (net (code "68") (name "Net-(IC3A-8Q)") (class "Default")
      (node (ref "IC3") (pin "19") (pinfunction "8Q_19") (pintype "tri_state"))
      (node (ref "OUT3-4") (pin "7") (pinfunction "7_7") (pintype "passive"))
    )
    (net (code "69") (name "Net-(IC4A-1Q)") (class "Default")
      (node (ref "IC4") (pin "2") (pinfunction "1Q_2") (pintype "tri_state"))
      (node (ref "OUT3-4") (pin "10") (pinfunction "10_10") (pintype "passive"))
    )
    (net (code "70") (name "Net-(IC4A-2Q)") (class "Default")
      (node (ref "IC4") (pin "5") (pinfunction "2Q_5") (pintype "tri_state"))
      (node (ref "OUT3-4") (pin "12") (pinfunction "12_12") (pintype "passive"))
    )
    (net (code "71") (name "Net-(IC4A-3Q)") (class "Default")
      (node (ref "IC4") (pin "6") (pinfunction "3Q_6") (pintype "tri_state"))
      (node (ref "OUT3-4") (pin "14") (pinfunction "14_14") (pintype "passive"))
    )
    (net (code "72") (name "Net-(IC4A-4Q)") (class "Default")
      (node (ref "IC4") (pin "9") (pinfunction "4Q_9") (pintype "tri_state"))
      (node (ref "OUT3-4") (pin "16") (pinfunction "16_16") (pintype "passive"))
    )
    (net (code "73") (name "Net-(IC4A-5Q)") (class "Default")
      (node (ref "IC4") (pin "12") (pinfunction "5Q_12") (pintype "tri_state"))
      (node (ref "OUT3-4") (pin "9") (pinfunction "9_9") (pintype "passive"))
    )
    (net (code "74") (name "Net-(IC4A-6Q)") (class "Default")
      (node (ref "IC4") (pin "15") (pinfunction "6Q_15") (pintype "tri_state"))
      (node (ref "OUT3-4") (pin "11") (pinfunction "11_11") (pintype "passive"))
    )
    (net (code "75") (name "Net-(IC4A-7Q)") (class "Default")
      (node (ref "IC4") (pin "16") (pinfunction "7Q_16") (pintype "tri_state"))
      (node (ref "OUT3-4") (pin "13") (pinfunction "13_13") (pintype "passive"))
    )
    (net (code "76") (name "Net-(IC4A-8Q)") (class "Default")
      (node (ref "IC4") (pin "19") (pinfunction "8Q_19") (pintype "tri_state"))
      (node (ref "OUT3-4") (pin "15") (pinfunction "15_15") (pintype "passive"))
    )
    (net (code "77") (name "Net-(IC5A-1Q)") (class "Default")
      (node (ref "IC5") (pin "2") (pinfunction "1Q_2") (pintype "tri_state"))
      (node (ref "OUT5-6") (pin "2") (pinfunction "2_2") (pintype "passive"))
    )
    (net (code "78") (name "Net-(IC5A-2Q)") (class "Default")
      (node (ref "IC5") (pin "5") (pinfunction "2Q_5") (pintype "tri_state"))
      (node (ref "OUT5-6") (pin "4") (pinfunction "4_4") (pintype "passive"))
    )
    (net (code "79") (name "Net-(IC5A-3Q)") (class "Default")
      (node (ref "IC5") (pin "6") (pinfunction "3Q_6") (pintype "tri_state"))
      (node (ref "OUT5-6") (pin "6") (pinfunction "6_6") (pintype "passive"))
    )
    (net (code "80") (name "Net-(IC5A-4Q)") (class "Default")
      (node (ref "IC5") (pin "9") (pinfunction "4Q_9") (pintype "tri_state"))
      (node (ref "OUT5-6") (pin "8") (pinfunction "8_8") (pintype "passive"))
    )
    (net (code "81") (name "Net-(IC5A-5Q)") (class "Default")
      (node (ref "IC5") (pin "12") (pinfunction "5Q_12") (pintype "tri_state"))
      (node (ref "OUT5-6") (pin "1") (pinfunction "1_1") (pintype "passive"))
    )
    (net (code "82") (name "Net-(IC5A-6Q)") (class "Default")
      (node (ref "IC5") (pin "15") (pinfunction "6Q_15") (pintype "tri_state"))
      (node (ref "OUT5-6") (pin "3") (pinfunction "3_3") (pintype "passive"))
    )
    (net (code "83") (name "Net-(IC5A-7Q)") (class "Default")
      (node (ref "IC5") (pin "16") (pinfunction "7Q_16") (pintype "tri_state"))
      (node (ref "OUT5-6") (pin "5") (pinfunction "5_5") (pintype "passive"))
    )
    (net (code "84") (name "Net-(IC5A-8Q)") (class "Default")
      (node (ref "IC5") (pin "19") (pinfunction "8Q_19") (pintype "tri_state"))
      (node (ref "OUT5-6") (pin "7") (pinfunction "7_7") (pintype "passive"))
    )
    (net (code "85") (name "Net-(IC6A-1Q)") (class "Default")
      (node (ref "IC6") (pin "2") (pinfunction "1Q_2") (pintype "tri_state"))
      (node (ref "OUT5-6") (pin "10") (pinfunction "10_10") (pintype "passive"))
    )
    (net (code "86") (name "Net-(IC6A-2Q)") (class "Default")
      (node (ref "IC6") (pin "5") (pinfunction "2Q_5") (pintype "tri_state"))
      (node (ref "OUT5-6") (pin "12") (pinfunction "12_12") (pintype "passive"))
    )
    (net (code "87") (name "Net-(IC6A-3Q)") (class "Default")
      (node (ref "IC6") (pin "6") (pinfunction "3Q_6") (pintype "tri_state"))
      (node (ref "OUT5-6") (pin "14") (pinfunction "14_14") (pintype "passive"))
    )
    (net (code "88") (name "Net-(IC6A-4Q)") (class "Default")
      (node (ref "IC6") (pin "9") (pinfunction "4Q_9") (pintype "tri_state"))
      (node (ref "OUT5-6") (pin "16") (pinfunction "16_16") (pintype "passive"))
    )
    (net (code "89") (name "Net-(IC6A-5Q)") (class "Default")
      (node (ref "IC6") (pin "12") (pinfunction "5Q_12") (pintype "tri_state"))
      (node (ref "OUT5-6") (pin "9") (pinfunction "9_9") (pintype "passive"))
    )
    (net (code "90") (name "Net-(IC6A-6Q)") (class "Default")
      (node (ref "IC6") (pin "15") (pinfunction "6Q_15") (pintype "tri_state"))
      (node (ref "OUT5-6") (pin "11") (pinfunction "11_11") (pintype "passive"))
    )
    (net (code "91") (name "Net-(IC6A-7Q)") (class "Default")
      (node (ref "IC6") (pin "16") (pinfunction "7Q_16") (pintype "tri_state"))
      (node (ref "OUT5-6") (pin "13") (pinfunction "13_13") (pintype "passive"))
    )
    (net (code "92") (name "Net-(IC6A-8Q)") (class "Default")
      (node (ref "IC6") (pin "19") (pinfunction "8Q_19") (pintype "tri_state"))
      (node (ref "OUT5-6") (pin "15") (pinfunction "15_15") (pintype "passive"))
    )
    (net (code "93") (name "Net-(IC7A-1Q)") (class "Default")
      (node (ref "IC7") (pin "2") (pinfunction "1Q_2") (pintype "tri_state"))
      (node (ref "OUT7-8") (pin "2") (pinfunction "2_2") (pintype "passive"))
    )
    (net (code "94") (name "Net-(IC7A-2Q)") (class "Default")
      (node (ref "IC7") (pin "5") (pinfunction "2Q_5") (pintype "tri_state"))
      (node (ref "OUT7-8") (pin "4") (pinfunction "4_4") (pintype "passive"))
    )
    (net (code "95") (name "Net-(IC7A-3Q)") (class "Default")
      (node (ref "IC7") (pin "6") (pinfunction "3Q_6") (pintype "tri_state"))
      (node (ref "OUT7-8") (pin "6") (pinfunction "6_6") (pintype "passive"))
    )
    (net (code "96") (name "Net-(IC7A-4Q)") (class "Default")
      (node (ref "IC7") (pin "9") (pinfunction "4Q_9") (pintype "tri_state"))
      (node (ref "OUT7-8") (pin "8") (pinfunction "8_8") (pintype "passive"))
    )
    (net (code "97") (name "Net-(IC7A-5Q)") (class "Default")
      (node (ref "IC7") (pin "12") (pinfunction "5Q_12") (pintype "tri_state"))
      (node (ref "OUT7-8") (pin "1") (pinfunction "1_1") (pintype "passive"))
    )
    (net (code "98") (name "Net-(IC7A-6Q)") (class "Default")
      (node (ref "IC7") (pin "15") (pinfunction "6Q_15") (pintype "tri_state"))
      (node (ref "OUT7-8") (pin "3") (pinfunction "3_3") (pintype "passive"))
    )
    (net (code "99") (name "Net-(IC7A-7Q)") (class "Default")
      (node (ref "IC7") (pin "16") (pinfunction "7Q_16") (pintype "tri_state"))
      (node (ref "OUT7-8") (pin "5") (pinfunction "5_5") (pintype "passive"))
    )
    (net (code "100") (name "Net-(IC7A-8Q)") (class "Default")
      (node (ref "IC7") (pin "19") (pinfunction "8Q_19") (pintype "tri_state"))
      (node (ref "OUT7-8") (pin "7") (pinfunction "7_7") (pintype "passive"))
    )
    (net (code "101") (name "Net-(IC8A-1Q)") (class "Default")
      (node (ref "IC8") (pin "2") (pinfunction "1Q_2") (pintype "tri_state"))
      (node (ref "OUT7-8") (pin "10") (pinfunction "10_10") (pintype "passive"))
    )
    (net (code "102") (name "Net-(IC8A-2Q)") (class "Default")
      (node (ref "IC8") (pin "5") (pinfunction "2Q_5") (pintype "tri_state"))
      (node (ref "OUT7-8") (pin "12") (pinfunction "12_12") (pintype "passive"))
    )
    (net (code "103") (name "Net-(IC8A-3Q)") (class "Default")
      (node (ref "IC8") (pin "6") (pinfunction "3Q_6") (pintype "tri_state"))
      (node (ref "OUT7-8") (pin "14") (pinfunction "14_14") (pintype "passive"))
    )
    (net (code "104") (name "Net-(IC8A-4Q)") (class "Default")
      (node (ref "IC8") (pin "9") (pinfunction "4Q_9") (pintype "tri_state"))
      (node (ref "OUT7-8") (pin "16") (pinfunction "16_16") (pintype "passive"))
    )
    (net (code "105") (name "Net-(IC8A-5Q)") (class "Default")
      (node (ref "IC8") (pin "12") (pinfunction "5Q_12") (pintype "tri_state"))
      (node (ref "OUT7-8") (pin "9") (pinfunction "9_9") (pintype "passive"))
    )
    (net (code "106") (name "Net-(IC8A-6Q)") (class "Default")
      (node (ref "IC8") (pin "15") (pinfunction "6Q_15") (pintype "tri_state"))
      (node (ref "OUT7-8") (pin "11") (pinfunction "11_11") (pintype "passive"))
    )
    (net (code "107") (name "Net-(IC8A-7Q)") (class "Default")
      (node (ref "IC8") (pin "16") (pinfunction "7Q_16") (pintype "tri_state"))
      (node (ref "OUT7-8") (pin "13") (pinfunction "13_13") (pintype "passive"))
    )
    (net (code "108") (name "Net-(IC8A-8Q)") (class "Default")
      (node (ref "IC8") (pin "19") (pinfunction "8Q_19") (pintype "tri_state"))
      (node (ref "OUT7-8") (pin "15") (pinfunction "15_15") (pintype "passive"))
    )
    (net (code "109") (name "Net-(IC11A-1D)") (class "Default")
      (node (ref "IC11") (pin "3") (pinfunction "1D_3") (pintype "input"))
      (node (ref "IN1-2") (pin "2") (pinfunction "2_2") (pintype "passive"))
    )
    (net (code "110") (name "Net-(IC11A-2D)") (class "Default")
      (node (ref "IC11") (pin "4") (pinfunction "2D_4") (pintype "input"))
      (node (ref "IN1-2") (pin "4") (pinfunction "4_4") (pintype "passive"))
    )
    (net (code "111") (name "Net-(IC11A-3D)") (class "Default")
      (node (ref "IC11") (pin "7") (pinfunction "3D_7") (pintype "input"))
      (node (ref "IN1-2") (pin "6") (pinfunction "6_6") (pintype "passive"))
    )
    (net (code "112") (name "Net-(IC11A-4D)") (class "Default")
      (node (ref "IC11") (pin "8") (pinfunction "4D_8") (pintype "input"))
      (node (ref "IN1-2") (pin "8") (pinfunction "8_8") (pintype "passive"))
    )
    (net (code "113") (name "Net-(IC11A-5D)") (class "Default")
      (node (ref "IC11") (pin "13") (pinfunction "5D_13") (pintype "input"))
      (node (ref "IN1-2") (pin "1") (pinfunction "1_1") (pintype "passive"))
    )
    (net (code "114") (name "Net-(IC11A-6D)") (class "Default")
      (node (ref "IC11") (pin "14") (pinfunction "6D_14") (pintype "input"))
      (node (ref "IN1-2") (pin "3") (pinfunction "3_3") (pintype "passive"))
    )
    (net (code "115") (name "Net-(IC11A-7D)") (class "Default")
      (node (ref "IC11") (pin "17") (pinfunction "7D_17") (pintype "input"))
      (node (ref "IN1-2") (pin "5") (pinfunction "5_5") (pintype "passive"))
    )
    (net (code "116") (name "Net-(IC11A-8D)") (class "Default")
      (node (ref "IC11") (pin "18") (pinfunction "8D_18") (pintype "input"))
      (node (ref "IN1-2") (pin "7") (pinfunction "7_7") (pintype "passive"))
    )
    (net (code "117") (name "Net-(IC12A-1D)") (class "Default")
      (node (ref "IC12") (pin "3") (pinfunction "1D_3") (pintype "input"))
      (node (ref "IN1-2") (pin "10") (pinfunction "10_10") (pintype "passive"))
    )
    (net (code "118") (name "Net-(IC12A-2D)") (class "Default")
      (node (ref "IC12") (pin "4") (pinfunction "2D_4") (pintype "input"))
      (node (ref "IN1-2") (pin "12") (pinfunction "12_12") (pintype "passive"))
    )
    (net (code "119") (name "Net-(IC12A-3D)") (class "Default")
      (node (ref "IC12") (pin "7") (pinfunction "3D_7") (pintype "input"))
      (node (ref "IN1-2") (pin "14") (pinfunction "14_14") (pintype "passive"))
    )
    (net (code "120") (name "Net-(IC12A-4D)") (class "Default")
      (node (ref "IC12") (pin "8") (pinfunction "4D_8") (pintype "input"))
      (node (ref "IN1-2") (pin "16") (pinfunction "16_16") (pintype "passive"))
    )
    (net (code "121") (name "Net-(IC12A-5D)") (class "Default")
      (node (ref "IC12") (pin "13") (pinfunction "5D_13") (pintype "input"))
      (node (ref "IN1-2") (pin "9") (pinfunction "9_9") (pintype "passive"))
    )
    (net (code "122") (name "Net-(IC12A-6D)") (class "Default")
      (node (ref "IC12") (pin "14") (pinfunction "6D_14") (pintype "input"))
      (node (ref "IN1-2") (pin "11") (pinfunction "11_11") (pintype "passive"))
    )
    (net (code "123") (name "Net-(IC12A-7D)") (class "Default")
      (node (ref "IC12") (pin "17") (pinfunction "7D_17") (pintype "input"))
      (node (ref "IN1-2") (pin "13") (pinfunction "13_13") (pintype "passive"))
    )
    (net (code "124") (name "Net-(IC12A-8D)") (class "Default")
      (node (ref "IC12") (pin "18") (pinfunction "8D_18") (pintype "input"))
      (node (ref "IN1-2") (pin "15") (pinfunction "15_15") (pintype "passive"))
    )
    (net (code "125") (name "Net-(IC13A-1D)") (class "Default")
      (node (ref "IC13") (pin "3") (pinfunction "1D_3") (pintype "input"))
      (node (ref "IN3-4") (pin "2") (pinfunction "2_2") (pintype "passive"))
    )
    (net (code "126") (name "Net-(IC13A-2D)") (class "Default")
      (node (ref "IC13") (pin "4") (pinfunction "2D_4") (pintype "input"))
      (node (ref "IN3-4") (pin "4") (pinfunction "4_4") (pintype "passive"))
    )
    (net (code "127") (name "Net-(IC13A-3D)") (class "Default")
      (node (ref "IC13") (pin "7") (pinfunction "3D_7") (pintype "input"))
      (node (ref "IN3-4") (pin "6") (pinfunction "6_6") (pintype "passive"))
    )
    (net (code "128") (name "Net-(IC13A-4D)") (class "Default")
      (node (ref "IC13") (pin "8") (pinfunction "4D_8") (pintype "input"))
      (node (ref "IN3-4") (pin "8") (pinfunction "8_8") (pintype "passive"))
    )
    (net (code "129") (name "Net-(IC13A-5D)") (class "Default")
      (node (ref "IC13") (pin "13") (pinfunction "5D_13") (pintype "input"))
      (node (ref "IN3-4") (pin "1") (pinfunction "1_1") (pintype "passive"))
    )
    (net (code "130") (name "Net-(IC13A-6D)") (class "Default")
      (node (ref "IC13") (pin "14") (pinfunction "6D_14") (pintype "input"))
      (node (ref "IN3-4") (pin "3") (pinfunction "3_3") (pintype "passive"))
    )
    (net (code "131") (name "Net-(IC13A-7D)") (class "Default")
      (node (ref "IC13") (pin "17") (pinfunction "7D_17") (pintype "input"))
      (node (ref "IN3-4") (pin "5") (pinfunction "5_5") (pintype "passive"))
    )
    (net (code "132") (name "Net-(IC13A-8D)") (class "Default")
      (node (ref "IC13") (pin "18") (pinfunction "8D_18") (pintype "input"))
      (node (ref "IN3-4") (pin "7") (pinfunction "7_7") (pintype "passive"))
    )
    (net (code "133") (name "Net-(IC14A-1D)") (class "Default")
      (node (ref "IC14") (pin "3") (pinfunction "1D_3") (pintype "input"))
      (node (ref "IN3-4") (pin "10") (pinfunction "10_10") (pintype "passive"))
    )
    (net (code "134") (name "Net-(IC14A-2D)") (class "Default")
      (node (ref "IC14") (pin "4") (pinfunction "2D_4") (pintype "input"))
      (node (ref "IN3-4") (pin "12") (pinfunction "12_12") (pintype "passive"))
    )
    (net (code "135") (name "Net-(IC14A-3D)") (class "Default")
      (node (ref "IC14") (pin "7") (pinfunction "3D_7") (pintype "input"))
      (node (ref "IN3-4") (pin "14") (pinfunction "14_14") (pintype "passive"))
    )
    (net (code "136") (name "Net-(IC14A-4D)") (class "Default")
      (node (ref "IC14") (pin "8") (pinfunction "4D_8") (pintype "input"))
      (node (ref "IN3-4") (pin "16") (pinfunction "16_16") (pintype "passive"))
    )
    (net (code "137") (name "Net-(IC14A-5D)") (class "Default")
      (node (ref "IC14") (pin "13") (pinfunction "5D_13") (pintype "input"))
      (node (ref "IN3-4") (pin "9") (pinfunction "9_9") (pintype "passive"))
    )
    (net (code "138") (name "Net-(IC14A-6D)") (class "Default")
      (node (ref "IC14") (pin "14") (pinfunction "6D_14") (pintype "input"))
      (node (ref "IN3-4") (pin "11") (pinfunction "11_11") (pintype "passive"))
    )
    (net (code "139") (name "Net-(IC14A-7D)") (class "Default")
      (node (ref "IC14") (pin "17") (pinfunction "7D_17") (pintype "input"))
      (node (ref "IN3-4") (pin "13") (pinfunction "13_13") (pintype "passive"))
    )
    (net (code "140") (name "Net-(IC14A-8D)") (class "Default")
      (node (ref "IC14") (pin "18") (pinfunction "8D_18") (pintype "input"))
      (node (ref "IN3-4") (pin "15") (pinfunction "15_15") (pintype "passive"))
    )
    (net (code "141") (name "Net-(IC15A-1D)") (class "Default")
      (node (ref "IC15") (pin "3") (pinfunction "1D_3") (pintype "input"))
      (node (ref "IN5-6") (pin "2") (pinfunction "2_2") (pintype "passive"))
    )
    (net (code "142") (name "Net-(IC15A-2D)") (class "Default")
      (node (ref "IC15") (pin "4") (pinfunction "2D_4") (pintype "input"))
      (node (ref "IN5-6") (pin "4") (pinfunction "4_4") (pintype "passive"))
    )
    (net (code "143") (name "Net-(IC15A-3D)") (class "Default")
      (node (ref "IC15") (pin "7") (pinfunction "3D_7") (pintype "input"))
      (node (ref "IN5-6") (pin "6") (pinfunction "6_6") (pintype "passive"))
    )
    (net (code "144") (name "Net-(IC15A-4D)") (class "Default")
      (node (ref "IC15") (pin "8") (pinfunction "4D_8") (pintype "input"))
      (node (ref "IN5-6") (pin "8") (pinfunction "8_8") (pintype "passive"))
    )
    (net (code "145") (name "Net-(IC15A-5D)") (class "Default")
      (node (ref "IC15") (pin "13") (pinfunction "5D_13") (pintype "input"))
      (node (ref "IN5-6") (pin "1") (pinfunction "1_1") (pintype "passive"))
    )
    (net (code "146") (name "Net-(IC15A-6D)") (class "Default")
      (node (ref "IC15") (pin "14") (pinfunction "6D_14") (pintype "input"))
      (node (ref "IN5-6") (pin "3") (pinfunction "3_3") (pintype "passive"))
    )
    (net (code "147") (name "Net-(IC15A-7D)") (class "Default")
      (node (ref "IC15") (pin "17") (pinfunction "7D_17") (pintype "input"))
      (node (ref "IN5-6") (pin "5") (pinfunction "5_5") (pintype "passive"))
    )
    (net (code "148") (name "Net-(IC15A-8D)") (class "Default")
      (node (ref "IC15") (pin "18") (pinfunction "8D_18") (pintype "input"))
      (node (ref "IN5-6") (pin "7") (pinfunction "7_7") (pintype "passive"))
    )
    (net (code "149") (name "Net-(IC16A-1D)") (class "Default")
      (node (ref "IC16") (pin "3") (pinfunction "1D_3") (pintype "input"))
      (node (ref "IN5-6") (pin "10") (pinfunction "10_10") (pintype "passive"))
    )
    (net (code "150") (name "Net-(IC16A-2D)") (class "Default")
      (node (ref "IC16") (pin "4") (pinfunction "2D_4") (pintype "input"))
      (node (ref "IN5-6") (pin "12") (pinfunction "12_12") (pintype "passive"))
    )
    (net (code "151") (name "Net-(IC16A-3D)") (class "Default")
      (node (ref "IC16") (pin "7") (pinfunction "3D_7") (pintype "input"))
      (node (ref "IN5-6") (pin "14") (pinfunction "14_14") (pintype "passive"))
    )
    (net (code "152") (name "Net-(IC16A-4D)") (class "Default")
      (node (ref "IC16") (pin "8") (pinfunction "4D_8") (pintype "input"))
      (node (ref "IN5-6") (pin "16") (pinfunction "16_16") (pintype "passive"))
    )
    (net (code "153") (name "Net-(IC16A-5D)") (class "Default")
      (node (ref "IC16") (pin "13") (pinfunction "5D_13") (pintype "input"))
      (node (ref "IN5-6") (pin "9") (pinfunction "9_9") (pintype "passive"))
    )
    (net (code "154") (name "Net-(IC16A-6D)") (class "Default")
      (node (ref "IC16") (pin "14") (pinfunction "6D_14") (pintype "input"))
      (node (ref "IN5-6") (pin "11") (pinfunction "11_11") (pintype "passive"))
    )
    (net (code "155") (name "Net-(IC16A-7D)") (class "Default")
      (node (ref "IC16") (pin "17") (pinfunction "7D_17") (pintype "input"))
      (node (ref "IN5-6") (pin "13") (pinfunction "13_13") (pintype "passive"))
    )
    (net (code "156") (name "Net-(IC16A-8D)") (class "Default")
      (node (ref "IC16") (pin "18") (pinfunction "8D_18") (pintype "input"))
      (node (ref "IN5-6") (pin "15") (pinfunction "15_15") (pintype "passive"))
    )
    (net (code "157") (name "Net-(IC17A-EXTAL)") (class "Default")
      (node (ref "C2") (pin "1") (pinfunction "1_1") (pintype "passive"))
      (node (ref "IC17") (pin "39") (pinfunction "EXTAL_39") (pintype "input"))
      (node (ref "Q1") (pin "1") (pinfunction "1_1") (pintype "passive"))
    )
    (net (code "158") (name "Net-(IC17A-XTAL)") (class "Default")
      (node (ref "C1") (pin "2") (pinfunction "2_2") (pintype "passive"))
      (node (ref "IC17") (pin "38") (pinfunction "XTAL_38") (pintype "input"))
      (node (ref "Q1") (pin "2") (pinfunction "2_2") (pintype "passive"))
    )
    (net (code "159") (name "Net-(IC18A-I0)") (class "Default")
      (node (ref "C3") (pin "1") (pinfunction "1_1") (pintype "passive"))
      (node (ref "IC18") (pin "1") (pinfunction "I0_1") (pintype "input"))
      (node (ref "R1") (pin "1") (pinfunction "1_1") (pintype "passive"))
    )
    (net (code "160") (name "Net-(IC18A-I1)") (class "Default")
      (node (ref "IC18") (pin "2") (pinfunction "I1_2") (pintype "input"))
      (node (ref "JP1") (pin "2") (pinfunction "2_2") (pintype "passive"))
      (node (ref "R2") (pin "1") (pinfunction "1_1") (pintype "passive"))
    )
    (net (code "161") (name "Net-(IC18A-O)") (class "Default")
      (node (ref "IC18") (pin "3") (pinfunction "O_3") (pintype "output"))
      (node (ref "IC18") (pin "4") (pinfunction "I0_4") (pintype "input"))
      (node (ref "IC18") (pin "5") (pinfunction "I1_5") (pintype "input"))
    )
    (net (code "162") (name "Net-(IC18C-O)") (class "Default")
      (node (ref "IC18") (pin "8") (pinfunction "O_8") (pintype "output"))
      (node (ref "IC28") (pin "1") (pinfunction "G_1") (pintype "input"))
    )
    (net (code "163") (name "Net-(IC18D-I0)") (class "Default")
      (node (ref "IC18") (pin "12") (pinfunction "I0_12") (pintype "input"))
      (node (ref "IC18") (pin "13") (pinfunction "I1_13") (pintype "input"))
      (node (ref "IC21") (pin "5") (pinfunction "RTS_5") (pintype "output"))
    )
    (net (code "164") (name "Net-(IC18D-O)") (class "Default")
      (node (ref "IC18") (pin "11") (pinfunction "O_11") (pintype "output"))
      (node (ref "LED1") (pin "K") (pinfunction "C_K") (pintype "passive"))
    )
    (net (code "165") (name "Net-(IC19A-G2B)") (class "Default")
      (node (ref "IC19") (pin "5") (pinfunction "G2B_5") (pintype "input"))
      (node (ref "IC28") (pin "4") (pinfunction "Y0_4") (pintype "output"))
    )
    (net (code "166") (name "Net-(IC20A-C1+)") (class "Default")
      (node (ref "C8") (pin "1") (pinfunction "1_1") (pintype "passive"))
      (node (ref "IC20") (pin "1") (pinfunction "C1+_1") (pintype "bidirectional"))
    )
    (net (code "167") (name "Net-(IC20A-C1-)") (class "Default")
      (node (ref "C8") (pin "2") (pinfunction "2_2") (pintype "passive"))
      (node (ref "IC20") (pin "3") (pinfunction "C1-_3") (pintype "bidirectional"))
    )
    (net (code "168") (name "Net-(IC20A-C2+)") (class "Default")
      (node (ref "C9") (pin "1") (pinfunction "1_1") (pintype "passive"))
      (node (ref "IC20") (pin "4") (pinfunction "C2+_4") (pintype "bidirectional"))
    )
    (net (code "169") (name "Net-(IC20A-C2-)") (class "Default")
      (node (ref "C9") (pin "2") (pinfunction "2_2") (pintype "passive"))
      (node (ref "IC20") (pin "5") (pinfunction "C2-_5") (pintype "bidirectional"))
    )
    (net (code "170") (name "Net-(IC20A-R2IN)") (class "Default")
      (node (ref "IC20") (pin "7") (pinfunction "T2OUT_7") (pintype "output"))
      (node (ref "IC20") (pin "8") (pinfunction "R2IN_8") (pintype "input"))
    )
    (net (code "171") (name "Net-(IC20A-V+)") (class "Default")
      (node (ref "C10") (pin "2") (pinfunction "2_2") (pintype "passive"))
      (node (ref "IC20") (pin "2") (pinfunction "V+_2") (pintype "bidirectional"))
    )
    (net (code "172") (name "Net-(IC20A-V-)") (class "Default")
      (node (ref "C11") (pin "1") (pinfunction "1_1") (pintype "passive"))
      (node (ref "IC20") (pin "6") (pinfunction "V-_6") (pintype "bidirectional"))
    )
    (net (code "173") (name "Net-(IC21A-CTS)") (class "Default")
      (node (ref "IC21") (pin "24") (pinfunction "CTS_24") (pintype "input"))
      (node (ref "JP2") (pin "1") (pinfunction "1_1") (pintype "passive"))
      (node (ref "R13") (pin "2") (pinfunction "2_2") (pintype "passive"))
    )
    (net (code "174") (name "Net-(IC21A-RXCLK)") (class "Default")
      (node (ref "IC21") (pin "3") (pinfunction "RXCLK_3") (pintype "input"))
      (node (ref "IC21") (pin "4") (pinfunction "TXCLK_4") (pintype "input"))
      (node (ref "IC27") (pin "5") (pinfunction "Q_5") (pintype "output"))
    )
    (net (code "175") (name "Net-(IC24A-CA1)") (class "Default")
      (node (ref "IC24") (pin "40") (pinfunction "CA1_40") (pintype "input"))
      (node (ref "IC27") (pin "9") (pinfunction "Q_9") (pintype "output"))
    )
    (net (code "176") (name "Net-(IC24A-CA2)") (class "Default")
      (node (ref "IC24") (pin "39") (pinfunction "CA2_39") (pintype "bidirectional"))
      (node (ref "IC25") (pin "1") (pinfunction "DIR_1") (pintype "input"))
    )
    (net (code "177") (name "Net-(IC24A-CB2)") (class "Default")
      (node (ref "IC24") (pin "19") (pinfunction "CB2_19") (pintype "bidirectional"))
      (node (ref "IC26") (pin "1") (pinfunction "DIR_1") (pintype "input"))
    )
    (net (code "178") (name "Net-(IC24A-PA0)") (class "Default")
      (node (ref "IC24") (pin "2") (pinfunction "PA0_2") (pintype "bidirectional"))
      (node (ref "IC25") (pin "18") (pinfunction "B1_18") (pintype "bidirectional"))
    )
    (net (code "179") (name "Net-(IC24A-PA1)") (class "Default")
      (node (ref "IC24") (pin "3") (pinfunction "PA1_3") (pintype "bidirectional"))
      (node (ref "IC25") (pin "17") (pinfunction "B2_17") (pintype "bidirectional"))
    )
    (net (code "180") (name "Net-(IC24A-PA2)") (class "Default")
      (node (ref "IC24") (pin "4") (pinfunction "PA2_4") (pintype "bidirectional"))
      (node (ref "IC25") (pin "16") (pinfunction "B3_16") (pintype "bidirectional"))
    )
    (net (code "181") (name "Net-(IC24A-PA3)") (class "Default")
      (node (ref "IC24") (pin "5") (pinfunction "PA3_5") (pintype "bidirectional"))
      (node (ref "IC25") (pin "15") (pinfunction "B4_15") (pintype "bidirectional"))
    )
    (net (code "182") (name "Net-(IC24A-PA4)") (class "Default")
      (node (ref "IC24") (pin "6") (pinfunction "PA4_6") (pintype "bidirectional"))
      (node (ref "IC25") (pin "14") (pinfunction "B5_14") (pintype "bidirectional"))
    )
    (net (code "183") (name "Net-(IC24A-PA5)") (class "Default")
      (node (ref "IC24") (pin "7") (pinfunction "PA5_7") (pintype "bidirectional"))
      (node (ref "IC25") (pin "13") (pinfunction "B6_13") (pintype "bidirectional"))
    )
    (net (code "184") (name "Net-(IC24A-PA6)") (class "Default")
      (node (ref "IC24") (pin "8") (pinfunction "PA6_8") (pintype "bidirectional"))
      (node (ref "IC25") (pin "12") (pinfunction "B7_12") (pintype "bidirectional"))
    )
    (net (code "185") (name "Net-(IC24A-PA7)") (class "Default")
      (node (ref "IC24") (pin "9") (pinfunction "PA7_9") (pintype "bidirectional"))
      (node (ref "IC25") (pin "11") (pinfunction "B8_11") (pintype "bidirectional"))
    )
    (net (code "186") (name "Net-(IC24A-PB0)") (class "Default")
      (node (ref "IC24") (pin "10") (pinfunction "PB0_10") (pintype "bidirectional"))
      (node (ref "IC26") (pin "18") (pinfunction "B1_18") (pintype "bidirectional"))
    )
    (net (code "187") (name "Net-(IC24A-PB1)") (class "Default")
      (node (ref "IC24") (pin "11") (pinfunction "PB1_11") (pintype "bidirectional"))
      (node (ref "IC26") (pin "17") (pinfunction "B2_17") (pintype "bidirectional"))
    )
    (net (code "188") (name "Net-(IC24A-PB2)") (class "Default")
      (node (ref "IC24") (pin "12") (pinfunction "PB2_12") (pintype "bidirectional"))
      (node (ref "IC26") (pin "16") (pinfunction "B3_16") (pintype "bidirectional"))
    )
    (net (code "189") (name "Net-(IC24A-PB3)") (class "Default")
      (node (ref "IC24") (pin "13") (pinfunction "PB3_13") (pintype "bidirectional"))
      (node (ref "IC26") (pin "15") (pinfunction "B4_15") (pintype "bidirectional"))
    )
    (net (code "190") (name "Net-(IC24A-PB4)") (class "Default")
      (node (ref "IC24") (pin "14") (pinfunction "PB4_14") (pintype "bidirectional"))
      (node (ref "IC26") (pin "14") (pinfunction "B5_14") (pintype "bidirectional"))
    )
    (net (code "191") (name "Net-(IC24A-PB5)") (class "Default")
      (node (ref "IC24") (pin "15") (pinfunction "PB5_15") (pintype "bidirectional"))
      (node (ref "IC26") (pin "13") (pinfunction "B6_13") (pintype "bidirectional"))
    )
    (net (code "192") (name "Net-(IC24A-PB6)") (class "Default")
      (node (ref "IC24") (pin "16") (pinfunction "PB6_16") (pintype "bidirectional"))
      (node (ref "IC26") (pin "12") (pinfunction "B7_12") (pintype "bidirectional"))
    )
    (net (code "193") (name "Net-(IC24A-PB7)") (class "Default")
      (node (ref "IC24") (pin "17") (pinfunction "PB7_17") (pintype "bidirectional"))
      (node (ref "IC26") (pin "11") (pinfunction "B8_11") (pintype "bidirectional"))
    )
    (net (code "194") (name "Net-(IC27A-CV)") (class "Default")
      (node (ref "C7") (pin "1") (pinfunction "1_1") (pintype "passive"))
      (node (ref "IC27") (pin "3") (pinfunction "CV_3") (pintype "input"))
    )
    (net (code "195") (name "Net-(IC27A-DIS)") (class "Default")
      (node (ref "IC27") (pin "1") (pinfunction "DIS_1") (pintype "input"))
      (node (ref "R10") (pin "2") (pinfunction "2_2") (pintype "passive"))
      (node (ref "R9") (pin "1") (pinfunction "1_1") (pintype "passive"))
    )
    (net (code "196") (name "Net-(IC27A-THR)") (class "Default")
      (node (ref "C6") (pin "1") (pinfunction "1_1") (pintype "passive"))
      (node (ref "IC27") (pin "2") (pinfunction "THR_2") (pintype "input"))
      (node (ref "IC27") (pin "6") (pinfunction "TR_6") (pintype "input"))
      (node (ref "R11") (pin "A") (pinfunction "A_A") (pintype "passive"))
      (node (ref "R11") (pin "S") (pinfunction "S_S") (pintype "passive"))
    )
    (net (code "197") (name "Net-(IC27B-CV)") (class "Default")
      (node (ref "C5") (pin "1") (pinfunction "1_1") (pintype "passive"))
      (node (ref "IC27") (pin "11") (pinfunction "CV_11") (pintype "input"))
    )
    (net (code "198") (name "Net-(IC27B-DIS)") (class "Default")
      (node (ref "IC27") (pin "13") (pinfunction "DIS_13") (pintype "input"))
      (node (ref "R3") (pin "1") (pinfunction "1_1") (pintype "passive"))
      (node (ref "R4") (pin "2") (pinfunction "2_2") (pintype "passive"))
    )
    (net (code "199") (name "Net-(IC27B-THR)") (class "Default")
      (node (ref "C4") (pin "1") (pinfunction "1_1") (pintype "passive"))
      (node (ref "IC27") (pin "12") (pinfunction "THR_12") (pintype "input"))
      (node (ref "IC27") (pin "8") (pinfunction "TR_8") (pintype "input"))
      (node (ref "R4") (pin "1") (pinfunction "1_1") (pintype "passive"))
    )
    (net (code "200") (name "Net-(LED1-PadA)") (class "Default")
      (node (ref "LED1") (pin "A") (pinfunction "A_A") (pintype "passive"))
      (node (ref "R12") (pin "1") (pinfunction "1_1") (pintype "passive"))
    )
    (net (code "201") (name "Net-(R10-Pad1)") (class "Default")
      (node (ref "R10") (pin "1") (pinfunction "1_1") (pintype "passive"))
      (node (ref "R11") (pin "E") (pinfunction "E_E") (pintype "passive"))
    )
    (net (code "202") (name "Net-(X1-Pad4)") (class "Default")
      (node (ref "X1") (pin "4") (pinfunction "4_4") (pintype "passive"))
      (node (ref "X1") (pin "6") (pinfunction "6_6") (pintype "passive"))
    )
    (net (code "203") (name "Net-(X1-Pad7)") (class "Default")
      (node (ref "X1") (pin "7") (pinfunction "7_7") (pintype "passive"))
      (node (ref "X1") (pin "8") (pinfunction "8_8") (pintype "passive"))
    )
    (net (code "204") (name "OUT00") (class "Default")
      (node (ref "IC1") (pin "11") (pinfunction "CLK_11") (pintype "input"))
      (node (ref "IC10") (pin "1") (pinfunction "0_1") (pintype "output"))
    )
    (net (code "205") (name "OUT01") (class "Default")
      (node (ref "IC10") (pin "2") (pinfunction "1_2") (pintype "output"))
      (node (ref "IC2") (pin "11") (pinfunction "CLK_11") (pintype "input"))
    )
    (net (code "206") (name "OUT02") (class "Default")
      (node (ref "IC10") (pin "3") (pinfunction "2_3") (pintype "output"))
      (node (ref "IC3") (pin "11") (pinfunction "CLK_11") (pintype "input"))
    )
    (net (code "207") (name "OUT03") (class "Default")
      (node (ref "IC10") (pin "4") (pinfunction "3_4") (pintype "output"))
      (node (ref "IC4") (pin "11") (pinfunction "CLK_11") (pintype "input"))
    )
    (net (code "208") (name "OUT04") (class "Default")
      (node (ref "IC10") (pin "5") (pinfunction "4_5") (pintype "output"))
      (node (ref "IC5") (pin "11") (pinfunction "CLK_11") (pintype "input"))
    )
    (net (code "209") (name "OUT05") (class "Default")
      (node (ref "IC10") (pin "6") (pinfunction "5_6") (pintype "output"))
      (node (ref "IC6") (pin "11") (pinfunction "CLK_11") (pintype "input"))
    )
    (net (code "210") (name "OUT06") (class "Default")
      (node (ref "IC10") (pin "7") (pinfunction "6_7") (pintype "output"))
      (node (ref "IC7") (pin "11") (pinfunction "CLK_11") (pintype "input"))
    )
    (net (code "211") (name "OUT07") (class "Default")
      (node (ref "IC10") (pin "8") (pinfunction "7_8") (pintype "output"))
      (node (ref "IC8") (pin "11") (pinfunction "CLK_11") (pintype "input"))
    )
    (net (code "212") (name "OUT08") (class "Default")
      (node (ref "IC10") (pin "9") (pinfunction "8_9") (pintype "output"))
    )
    (net (code "213") (name "OUT09") (class "Default")
      (node (ref "IC10") (pin "10") (pinfunction "9_10") (pintype "output"))
    )
    (net (code "214") (name "OUT10") (class "Default")
      (node (ref "IC10") (pin "11") (pinfunction "10_11") (pintype "output"))
    )
    (net (code "215") (name "OUT11") (class "Default")
      (node (ref "IC10") (pin "13") (pinfunction "11_13") (pintype "output"))
    )
    (net (code "216") (name "OUT12") (class "Default")
      (node (ref "IC10") (pin "14") (pinfunction "12_14") (pintype "output"))
    )
    (net (code "217") (name "OUT13") (class "Default")
      (node (ref "IC10") (pin "15") (pinfunction "13_15") (pintype "output"))
    )
    (net (code "218") (name "OUT14") (class "Default")
      (node (ref "IC10") (pin "16") (pinfunction "14_16") (pintype "output"))
    )
    (net (code "219") (name "OUT15") (class "Default")
      (node (ref "IC10") (pin "17") (pinfunction "15_17") (pintype "output"))
    )
    (net (code "220") (name "PIA-A0") (class "Default")
      (node (ref "IC1") (pin "3") (pinfunction "1D_3") (pintype "input"))
      (node (ref "IC11") (pin "2") (pinfunction "1Q_2") (pintype "tri_state"))
      (node (ref "IC12") (pin "2") (pinfunction "1Q_2") (pintype "tri_state"))
      (node (ref "IC13") (pin "2") (pinfunction "1Q_2") (pintype "tri_state"))
      (node (ref "IC14") (pin "2") (pinfunction "1Q_2") (pintype "tri_state"))
      (node (ref "IC15") (pin "2") (pinfunction "1Q_2") (pintype "tri_state"))
      (node (ref "IC16") (pin "2") (pinfunction "1Q_2") (pintype "tri_state"))
      (node (ref "IC2") (pin "3") (pinfunction "1D_3") (pintype "input"))
      (node (ref "IC25") (pin "2") (pinfunction "A1_2") (pintype "bidirectional"))
      (node (ref "IC3") (pin "3") (pinfunction "1D_3") (pintype "input"))
      (node (ref "IC4") (pin "3") (pinfunction "1D_3") (pintype "input"))
      (node (ref "IC5") (pin "3") (pinfunction "1D_3") (pintype "input"))
      (node (ref "IC6") (pin "3") (pinfunction "1D_3") (pintype "input"))
      (node (ref "IC7") (pin "3") (pinfunction "1D_3") (pintype "input"))
      (node (ref "IC8") (pin "3") (pinfunction "1D_3") (pintype "input"))
      (node (ref "SV9") (pin "1") (pinfunction "1_1") (pintype "passive"))
    )
    (net (code "221") (name "PIA-A1") (class "Default")
      (node (ref "IC1") (pin "4") (pinfunction "2D_4") (pintype "input"))
      (node (ref "IC11") (pin "5") (pinfunction "2Q_5") (pintype "tri_state"))
      (node (ref "IC12") (pin "5") (pinfunction "2Q_5") (pintype "tri_state"))
      (node (ref "IC13") (pin "5") (pinfunction "2Q_5") (pintype "tri_state"))
      (node (ref "IC14") (pin "5") (pinfunction "2Q_5") (pintype "tri_state"))
      (node (ref "IC15") (pin "5") (pinfunction "2Q_5") (pintype "tri_state"))
      (node (ref "IC16") (pin "5") (pinfunction "2Q_5") (pintype "tri_state"))
      (node (ref "IC2") (pin "4") (pinfunction "2D_4") (pintype "input"))
      (node (ref "IC25") (pin "3") (pinfunction "A2_3") (pintype "bidirectional"))
      (node (ref "IC3") (pin "4") (pinfunction "2D_4") (pintype "input"))
      (node (ref "IC4") (pin "4") (pinfunction "2D_4") (pintype "input"))
      (node (ref "IC5") (pin "4") (pinfunction "2D_4") (pintype "input"))
      (node (ref "IC6") (pin "4") (pinfunction "2D_4") (pintype "input"))
      (node (ref "IC7") (pin "4") (pinfunction "2D_4") (pintype "input"))
      (node (ref "IC8") (pin "4") (pinfunction "2D_4") (pintype "input"))
      (node (ref "SV9") (pin "2") (pinfunction "2_2") (pintype "passive"))
    )
    (net (code "222") (name "PIA-A2") (class "Default")
      (node (ref "IC1") (pin "7") (pinfunction "3D_7") (pintype "input"))
      (node (ref "IC11") (pin "6") (pinfunction "3Q_6") (pintype "tri_state"))
      (node (ref "IC12") (pin "6") (pinfunction "3Q_6") (pintype "tri_state"))
      (node (ref "IC13") (pin "6") (pinfunction "3Q_6") (pintype "tri_state"))
      (node (ref "IC14") (pin "6") (pinfunction "3Q_6") (pintype "tri_state"))
      (node (ref "IC15") (pin "6") (pinfunction "3Q_6") (pintype "tri_state"))
      (node (ref "IC16") (pin "6") (pinfunction "3Q_6") (pintype "tri_state"))
      (node (ref "IC2") (pin "7") (pinfunction "3D_7") (pintype "input"))
      (node (ref "IC25") (pin "4") (pinfunction "A3_4") (pintype "bidirectional"))
      (node (ref "IC3") (pin "7") (pinfunction "3D_7") (pintype "input"))
      (node (ref "IC4") (pin "7") (pinfunction "3D_7") (pintype "input"))
      (node (ref "IC5") (pin "7") (pinfunction "3D_7") (pintype "input"))
      (node (ref "IC6") (pin "7") (pinfunction "3D_7") (pintype "input"))
      (node (ref "IC7") (pin "7") (pinfunction "3D_7") (pintype "input"))
      (node (ref "IC8") (pin "7") (pinfunction "3D_7") (pintype "input"))
      (node (ref "SV9") (pin "3") (pinfunction "3_3") (pintype "passive"))
    )
    (net (code "223") (name "PIA-A3") (class "Default")
      (node (ref "IC1") (pin "8") (pinfunction "4D_8") (pintype "input"))
      (node (ref "IC11") (pin "9") (pinfunction "4Q_9") (pintype "tri_state"))
      (node (ref "IC12") (pin "9") (pinfunction "4Q_9") (pintype "tri_state"))
      (node (ref "IC13") (pin "9") (pinfunction "4Q_9") (pintype "tri_state"))
      (node (ref "IC14") (pin "9") (pinfunction "4Q_9") (pintype "tri_state"))
      (node (ref "IC15") (pin "9") (pinfunction "4Q_9") (pintype "tri_state"))
      (node (ref "IC16") (pin "9") (pinfunction "4Q_9") (pintype "tri_state"))
      (node (ref "IC2") (pin "8") (pinfunction "4D_8") (pintype "input"))
      (node (ref "IC25") (pin "5") (pinfunction "A4_5") (pintype "bidirectional"))
      (node (ref "IC3") (pin "8") (pinfunction "4D_8") (pintype "input"))
      (node (ref "IC4") (pin "8") (pinfunction "4D_8") (pintype "input"))
      (node (ref "IC5") (pin "8") (pinfunction "4D_8") (pintype "input"))
      (node (ref "IC6") (pin "8") (pinfunction "4D_8") (pintype "input"))
      (node (ref "IC7") (pin "8") (pinfunction "4D_8") (pintype "input"))
      (node (ref "IC8") (pin "8") (pinfunction "4D_8") (pintype "input"))
      (node (ref "SV9") (pin "4") (pinfunction "4_4") (pintype "passive"))
    )
    (net (code "224") (name "PIA-A4") (class "Default")
      (node (ref "IC1") (pin "13") (pinfunction "5D_13") (pintype "input"))
      (node (ref "IC11") (pin "12") (pinfunction "5Q_12") (pintype "tri_state"))
      (node (ref "IC12") (pin "12") (pinfunction "5Q_12") (pintype "tri_state"))
      (node (ref "IC13") (pin "12") (pinfunction "5Q_12") (pintype "tri_state"))
      (node (ref "IC14") (pin "12") (pinfunction "5Q_12") (pintype "tri_state"))
      (node (ref "IC15") (pin "12") (pinfunction "5Q_12") (pintype "tri_state"))
      (node (ref "IC16") (pin "12") (pinfunction "5Q_12") (pintype "tri_state"))
      (node (ref "IC2") (pin "13") (pinfunction "5D_13") (pintype "input"))
      (node (ref "IC25") (pin "6") (pinfunction "A5_6") (pintype "bidirectional"))
      (node (ref "IC3") (pin "13") (pinfunction "5D_13") (pintype "input"))
      (node (ref "IC4") (pin "13") (pinfunction "5D_13") (pintype "input"))
      (node (ref "IC5") (pin "13") (pinfunction "5D_13") (pintype "input"))
      (node (ref "IC6") (pin "13") (pinfunction "5D_13") (pintype "input"))
      (node (ref "IC7") (pin "13") (pinfunction "5D_13") (pintype "input"))
      (node (ref "IC8") (pin "13") (pinfunction "5D_13") (pintype "input"))
      (node (ref "SV9") (pin "5") (pinfunction "5_5") (pintype "passive"))
    )
    (net (code "225") (name "PIA-A5") (class "Default")
      (node (ref "IC1") (pin "14") (pinfunction "6D_14") (pintype "input"))
      (node (ref "IC11") (pin "15") (pinfunction "6Q_15") (pintype "tri_state"))
      (node (ref "IC12") (pin "15") (pinfunction "6Q_15") (pintype "tri_state"))
      (node (ref "IC13") (pin "15") (pinfunction "6Q_15") (pintype "tri_state"))
      (node (ref "IC14") (pin "15") (pinfunction "6Q_15") (pintype "tri_state"))
      (node (ref "IC15") (pin "15") (pinfunction "6Q_15") (pintype "tri_state"))
      (node (ref "IC16") (pin "15") (pinfunction "6Q_15") (pintype "tri_state"))
      (node (ref "IC2") (pin "14") (pinfunction "6D_14") (pintype "input"))
      (node (ref "IC25") (pin "7") (pinfunction "A6_7") (pintype "bidirectional"))
      (node (ref "IC3") (pin "14") (pinfunction "6D_14") (pintype "input"))
      (node (ref "IC4") (pin "14") (pinfunction "6D_14") (pintype "input"))
      (node (ref "IC5") (pin "14") (pinfunction "6D_14") (pintype "input"))
      (node (ref "IC6") (pin "14") (pinfunction "6D_14") (pintype "input"))
      (node (ref "IC7") (pin "14") (pinfunction "6D_14") (pintype "input"))
      (node (ref "IC8") (pin "14") (pinfunction "6D_14") (pintype "input"))
      (node (ref "SV9") (pin "6") (pinfunction "6_6") (pintype "passive"))
    )
    (net (code "226") (name "PIA-A6") (class "Default")
      (node (ref "IC1") (pin "17") (pinfunction "7D_17") (pintype "input"))
      (node (ref "IC11") (pin "16") (pinfunction "7Q_16") (pintype "tri_state"))
      (node (ref "IC12") (pin "16") (pinfunction "7Q_16") (pintype "tri_state"))
      (node (ref "IC13") (pin "16") (pinfunction "7Q_16") (pintype "tri_state"))
      (node (ref "IC14") (pin "16") (pinfunction "7Q_16") (pintype "tri_state"))
      (node (ref "IC15") (pin "16") (pinfunction "7Q_16") (pintype "tri_state"))
      (node (ref "IC16") (pin "16") (pinfunction "7Q_16") (pintype "tri_state"))
      (node (ref "IC2") (pin "17") (pinfunction "7D_17") (pintype "input"))
      (node (ref "IC25") (pin "8") (pinfunction "A7_8") (pintype "bidirectional"))
      (node (ref "IC3") (pin "17") (pinfunction "7D_17") (pintype "input"))
      (node (ref "IC4") (pin "17") (pinfunction "7D_17") (pintype "input"))
      (node (ref "IC5") (pin "17") (pinfunction "7D_17") (pintype "input"))
      (node (ref "IC6") (pin "17") (pinfunction "7D_17") (pintype "input"))
      (node (ref "IC7") (pin "17") (pinfunction "7D_17") (pintype "input"))
      (node (ref "IC8") (pin "17") (pinfunction "7D_17") (pintype "input"))
      (node (ref "SV9") (pin "7") (pinfunction "7_7") (pintype "passive"))
    )
    (net (code "227") (name "PIA-A7") (class "Default")
      (node (ref "IC1") (pin "18") (pinfunction "8D_18") (pintype "input"))
      (node (ref "IC11") (pin "19") (pinfunction "8Q_19") (pintype "tri_state"))
      (node (ref "IC12") (pin "19") (pinfunction "8Q_19") (pintype "tri_state"))
      (node (ref "IC13") (pin "19") (pinfunction "8Q_19") (pintype "tri_state"))
      (node (ref "IC14") (pin "19") (pinfunction "8Q_19") (pintype "tri_state"))
      (node (ref "IC15") (pin "19") (pinfunction "8Q_19") (pintype "tri_state"))
      (node (ref "IC16") (pin "19") (pinfunction "8Q_19") (pintype "tri_state"))
      (node (ref "IC2") (pin "18") (pinfunction "8D_18") (pintype "input"))
      (node (ref "IC25") (pin "9") (pinfunction "A8_9") (pintype "bidirectional"))
      (node (ref "IC3") (pin "18") (pinfunction "8D_18") (pintype "input"))
      (node (ref "IC4") (pin "18") (pinfunction "8D_18") (pintype "input"))
      (node (ref "IC5") (pin "18") (pinfunction "8D_18") (pintype "input"))
      (node (ref "IC6") (pin "18") (pinfunction "8D_18") (pintype "input"))
      (node (ref "IC7") (pin "18") (pinfunction "8D_18") (pintype "input"))
      (node (ref "IC8") (pin "18") (pinfunction "8D_18") (pintype "input"))
      (node (ref "SV9") (pin "8") (pinfunction "8_8") (pintype "passive"))
    )
    (net (code "228") (name "PIA-B0") (class "Default")
      (node (ref "IC10") (pin "23") (pinfunction "A_23") (pintype "input"))
      (node (ref "IC26") (pin "2") (pinfunction "A1_2") (pintype "bidirectional"))
      (node (ref "IC9") (pin "23") (pinfunction "A_23") (pintype "input"))
      (node (ref "SV9") (pin "13") (pinfunction "13_13") (pintype "passive"))
    )
    (net (code "229") (name "PIA-B1") (class "Default")
      (node (ref "IC10") (pin "22") (pinfunction "B_22") (pintype "input"))
      (node (ref "IC26") (pin "3") (pinfunction "A2_3") (pintype "bidirectional"))
      (node (ref "IC9") (pin "22") (pinfunction "B_22") (pintype "input"))
      (node (ref "SV9") (pin "14") (pinfunction "14_14") (pintype "passive"))
    )
    (net (code "230") (name "PIA-B2") (class "Default")
      (node (ref "IC10") (pin "21") (pinfunction "C_21") (pintype "input"))
      (node (ref "IC26") (pin "4") (pinfunction "A3_4") (pintype "bidirectional"))
      (node (ref "IC9") (pin "21") (pinfunction "C_21") (pintype "input"))
      (node (ref "SV9") (pin "15") (pinfunction "15_15") (pintype "passive"))
    )
    (net (code "231") (name "PIA-B3") (class "Default")
      (node (ref "IC10") (pin "20") (pinfunction "D_20") (pintype "input"))
      (node (ref "IC26") (pin "5") (pinfunction "A4_5") (pintype "bidirectional"))
      (node (ref "IC9") (pin "20") (pinfunction "D_20") (pintype "input"))
      (node (ref "SV9") (pin "16") (pinfunction "16_16") (pintype "passive"))
    )
    (net (code "232") (name "PIA-B4") (class "Default")
      (node (ref "IC26") (pin "6") (pinfunction "A5_6") (pintype "bidirectional"))
      (node (ref "IC9") (pin "18") (pinfunction "G1_18") (pintype "input"))
      (node (ref "SV9") (pin "17") (pinfunction "17_17") (pintype "passive"))
    )
    (net (code "233") (name "PIA-B5") (class "Default")
      (node (ref "IC10") (pin "18") (pinfunction "G1_18") (pintype "input"))
      (node (ref "IC26") (pin "7") (pinfunction "A6_7") (pintype "bidirectional"))
      (node (ref "SV9") (pin "18") (pinfunction "18_18") (pintype "passive"))
    )
    (net (code "234") (name "PIA-B6") (class "Default")
      (node (ref "IC26") (pin "8") (pinfunction "A7_8") (pintype "bidirectional"))
      (node (ref "SV9") (pin "19") (pinfunction "19_19") (pintype "passive"))
    )
    (net (code "235") (name "PIA-B7") (class "Default")
      (node (ref "IC26") (pin "9") (pinfunction "A8_9") (pintype "bidirectional"))
      (node (ref "SV9") (pin "20") (pinfunction "20_20") (pintype "passive"))
    )
    (net (code "236") (name "RX") (class "Default")
      (node (ref "IC20") (pin "12") (pinfunction "R1OUT_12") (pintype "output"))
      (node (ref "IC21") (pin "2") (pinfunction "RXDATA_2") (pintype "input"))
    )
    (net (code "237") (name "RXD") (class "Default")
      (node (ref "IC20") (pin "13") (pinfunction "R1IN_13") (pintype "input"))
      (node (ref "X1") (pin "3") (pinfunction "3_3") (pintype "passive"))
    )
    (net (code "238") (name "R{slash}~{W}") (class "Default")
      (node (ref "IC17") (pin "34") (pinfunction "R/~{W}_34") (pintype "output"))
      (node (ref "IC21") (pin "13") (pinfunction "R/~{W}_13") (pintype "input"))
      (node (ref "IC22") (pin "27") (pinfunction "~{WE}_27") (pintype "input"))
      (node (ref "IC24") (pin "21") (pinfunction "R/~{W}_21") (pintype "input"))
    )
    (net (code "239") (name "TX") (class "Default")
      (node (ref "IC20") (pin "11") (pinfunction "T1IN_11") (pintype "input"))
      (node (ref "IC21") (pin "6") (pinfunction "TXDATA_6") (pintype "output"))
    )
    (net (code "240") (name "TXD") (class "Default")
      (node (ref "IC20") (pin "14") (pinfunction "T1OUT_14") (pintype "output"))
      (node (ref "X1") (pin "2") (pinfunction "2_2") (pintype "passive"))
    )
    (net (code "241") (name "VCC") (class "Default")
      (node (ref "BYP1") (pin "1") (pinfunction "1_1") (pintype "passive"))
      (node (ref "BYP10") (pin "1") (pinfunction "1_1") (pintype "passive"))
      (node (ref "BYP11") (pin "1") (pinfunction "1_1") (pintype "passive"))
      (node (ref "BYP12") (pin "1") (pinfunction "1_1") (pintype "passive"))
      (node (ref "BYP13") (pin "1") (pinfunction "1_1") (pintype "passive"))
      (node (ref "BYP14") (pin "1") (pinfunction "1_1") (pintype "passive"))
      (node (ref "BYP15") (pin "1") (pinfunction "1_1") (pintype "passive"))
      (node (ref "BYP16") (pin "1") (pinfunction "1_1") (pintype "passive"))
      (node (ref "BYP17") (pin "1") (pinfunction "1_1") (pintype "passive"))
      (node (ref "BYP18") (pin "1") (pinfunction "1_1") (pintype "passive"))
      (node (ref "BYP19") (pin "1") (pinfunction "1_1") (pintype "passive"))
      (node (ref "BYP2") (pin "1") (pinfunction "1_1") (pintype "passive"))
      (node (ref "BYP20") (pin "1") (pinfunction "1_1") (pintype "passive"))
      (node (ref "BYP21") (pin "1") (pinfunction "1_1") (pintype "passive"))
      (node (ref "BYP22") (pin "1") (pinfunction "1_1") (pintype "passive"))
      (node (ref "BYP23") (pin "1") (pinfunction "1_1") (pintype "passive"))
      (node (ref "BYP24") (pin "1") (pinfunction "1_1") (pintype "passive"))
      (node (ref "BYP25") (pin "1") (pinfunction "1_1") (pintype "passive"))
      (node (ref "BYP26") (pin "1") (pinfunction "1_1") (pintype "passive"))
      (node (ref "BYP27") (pin "1") (pinfunction "1_1") (pintype "passive"))
      (node (ref "BYP28") (pin "1") (pinfunction "1_1") (pintype "passive"))
      (node (ref "BYP3") (pin "1") (pinfunction "1_1") (pintype "passive"))
      (node (ref "BYP4") (pin "1") (pinfunction "1_1") (pintype "passive"))
      (node (ref "BYP5") (pin "1") (pinfunction "1_1") (pintype "passive"))
      (node (ref "BYP6") (pin "1") (pinfunction "1_1") (pintype "passive"))
      (node (ref "BYP7") (pin "1") (pinfunction "1_1") (pintype "passive"))
      (node (ref "BYP8") (pin "1") (pinfunction "1_1") (pintype "passive"))
      (node (ref "BYP9") (pin "1") (pinfunction "1_1") (pintype "passive"))
      (node (ref "C10") (pin "1") (pinfunction "1_1") (pintype "passive"))
      (node (ref "IC11") (pin "11") (pinfunction "ENC_11") (pintype "input"))
      (node (ref "IC12") (pin "11") (pinfunction "ENC_11") (pintype "input"))
      (node (ref "IC13") (pin "11") (pinfunction "ENC_11") (pintype "input"))
      (node (ref "IC14") (pin "11") (pinfunction "ENC_11") (pintype "input"))
      (node (ref "IC15") (pin "11") (pinfunction "ENC_11") (pintype "input"))
      (node (ref "IC16") (pin "11") (pinfunction "ENC_11") (pintype "input"))
      (node (ref "IC17") (pin "35") (pinfunction "VCCSTB_35") (pintype "input"))
      (node (ref "IC17") (pin "36") (pinfunction "RE_36") (pintype "input"))
      (node (ref "IC17") (pin "8") (pinfunction "VCC_8") (pintype "power_in"))
      (node (ref "IC21") (pin "10") (pinfunction "CS1_10") (pintype "input"))
      (node (ref "IC21") (pin "12") (pinfunction "VCC_12") (pintype "power_in"))
      (node (ref "IC21") (pin "8") (pinfunction "CS0_8") (pintype "input"))
      (node (ref "IC22") (pin "26") (pinfunction "CS2_26") (pintype "input"))
      (node (ref "IC22") (pin "28") (pinfunction "VCC_28") (pintype "power_in"))
      (node (ref "IC23") (pin "1") (pinfunction "VPP_1") (pintype "input"))
      (node (ref "IC23") (pin "27") (pinfunction "~{PGM}_27") (pintype "passive"))
      (node (ref "IC23") (pin "28") (pinfunction "VCC_28") (pintype "power_in"))
      (node (ref "IC24") (pin "20") (pinfunction "VCC_20") (pintype "power_in"))
      (node (ref "IC24") (pin "22") (pinfunction "CS0_22") (pintype "input"))
      (node (ref "IC24") (pin "24") (pinfunction "CS1_24") (pintype "input"))
      (node (ref "IC27") (pin "10") (pinfunction "R_10") (pintype "input"))
      (node (ref "IC27") (pin "14") (pinfunction "V+_14") (pintype "power_in"))
      (node (ref "IC27") (pin "4") (pinfunction "R_4") (pintype "input"))
      (node (ref "JP2") (pin "2") (pinfunction "2_2") (pintype "passive"))
      (node (ref "R1") (pin "2") (pinfunction "2_2") (pintype "passive"))
      (node (ref "R12") (pin "2") (pinfunction "2_2") (pintype "passive"))
      (node (ref "R14") (pin "2") (pinfunction "2_2") (pintype "passive"))
      (node (ref "R2") (pin "2") (pinfunction "2_2") (pintype "passive"))
      (node (ref "R3") (pin "2") (pinfunction "2_2") (pintype "passive"))
      (node (ref "R5") (pin "2") (pinfunction "2_2") (pintype "passive"))
      (node (ref "R6") (pin "2") (pinfunction "2_2") (pintype "passive"))
      (node (ref "R7") (pin "2") (pinfunction "2_2") (pintype "passive"))
      (node (ref "R8") (pin "2") (pinfunction "2_2") (pintype "passive"))
      (node (ref "R9") (pin "2") (pinfunction "2_2") (pintype "passive"))
      (node (ref "SV9") (pin "11") (pinfunction "11_11") (pintype "passive"))
      (node (ref "SV9") (pin "12") (pinfunction "12_12") (pintype "passive"))
    )
    (net (code "242") (name "VMA") (class "Default")
      (node (ref "IC17") (pin "5") (pinfunction "VMA_5") (pintype "output"))
      (node (ref "IC18") (pin "9") (pinfunction "I0_9") (pintype "input"))
    )
    (net (code "243") (name "unconnected-(IC17A-BA-Pad7)") (class "Default")
      (node (ref "IC17") (pin "7") (pinfunction "BA_7") (pintype "output"))
    )
    (net (code "244") (name "unconnected-(IC19A-Y0-Pad15)") (class "Default")
      (node (ref "IC19") (pin "15") (pinfunction "Y0_15") (pintype "output"))
    )
    (net (code "245") (name "unconnected-(IC19A-Y1-Pad14)") (class "Default")
      (node (ref "IC19") (pin "14") (pinfunction "Y1_14") (pintype "output"))
    )
    (net (code "246") (name "unconnected-(IC19A-Y2-Pad13)") (class "Default")
      (node (ref "IC19") (pin "13") (pinfunction "Y2_13") (pintype "output"))
    )
    (net (code "247") (name "unconnected-(IC19A-Y3-Pad12)") (class "Default")
      (node (ref "IC19") (pin "12") (pinfunction "Y3_12") (pintype "output"))
    )
    (net (code "248") (name "unconnected-(IC19A-Y4-Pad11)") (class "Default")
      (node (ref "IC19") (pin "11") (pinfunction "Y4_11") (pintype "output"))
    )
    (net (code "249") (name "unconnected-(IC19A-Y5-Pad10)") (class "Default")
      (node (ref "IC19") (pin "10") (pinfunction "Y5_10") (pintype "output"))
    )
    (net (code "250") (name "unconnected-(IC20A-R2OUT-Pad9)") (class "Default")
      (node (ref "IC20") (pin "9") (pinfunction "R2OUT_9") (pintype "output"))
    )
    (net (code "251") (name "unconnected-(IC22-NC-Pad1)") (class "Default")
      (node (ref "IC22") (pin "1") (pinfunction "NC_1") (pintype "no_connect"))
    )
    (net (code "252") (name "unconnected-(IC28A-Y1-Pad5)") (class "Default")
      (node (ref "IC28") (pin "5") (pinfunction "Y1_5") (pintype "output"))
    )
    (net (code "253") (name "unconnected-(IC28B-Y0-Pad12)") (class "Default")
      (node (ref "IC28") (pin "12") (pinfunction "Y0_12") (pintype "output"))
    )
    (net (code "254") (name "unconnected-(IC28B-Y1-Pad11)") (class "Default")
      (node (ref "IC28") (pin "11") (pinfunction "Y1_11") (pintype "output"))
    )
    (net (code "255") (name "unconnected-(IC28B-Y2-Pad10)") (class "Default")
      (node (ref "IC28") (pin "10") (pinfunction "Y2_10") (pintype "output"))
    )
    (net (code "256") (name "unconnected-(IC28B-Y3-Pad9)") (class "Default")
      (node (ref "IC28") (pin "9") (pinfunction "Y3_9") (pintype "output"))
    )
    (net (code "257") (name "unconnected-(X1-Pad1)") (class "Default")
      (node (ref "X1") (pin "1") (pinfunction "1_1") (pintype "passive"))
    )
    (net (code "258") (name "unconnected-(X1-Pad9)") (class "Default")
      (node (ref "X1") (pin "9") (pinfunction "9_9") (pintype "passive"))
    )
    (net (code "259") (name "~{89AB}") (class "Default")
      (node (ref "IC22") (pin "20") (pinfunction "~{CS1}_20") (pintype "input"))
      (node (ref "IC22") (pin "22") (pinfunction "~{OE}_22") (pintype "input"))
      (node (ref "IC28") (pin "6") (pinfunction "Y2_6") (pintype "output"))
    )
    (net (code "260") (name "~{CDEF}") (class "Default")
      (node (ref "IC23") (pin "20") (pinfunction "~{CE}_20") (pintype "input"))
      (node (ref "IC23") (pin "22") (pinfunction "~{OE}_22") (pintype "input"))
      (node (ref "IC28") (pin "7") (pinfunction "Y3_7") (pintype "output"))
    )
    (net (code "261") (name "~{HLT}") (class "Default")
      (node (ref "IC17") (pin "2") (pinfunction "HALT_2") (pintype "input"))
      (node (ref "R5") (pin "1") (pinfunction "1_1") (pintype "passive"))
    )
    (net (code "262") (name "~{IO-E}") (class "Default")
      (node (ref "IC19") (pin "9") (pinfunction "Y6_9") (pintype "output"))
      (node (ref "IC24") (pin "23") (pinfunction "CS2_23") (pintype "input"))
    )
    (net (code "263") (name "~{IO-F}") (class "Default")
      (node (ref "IC19") (pin "7") (pinfunction "Y7_7") (pintype "output"))
      (node (ref "IC21") (pin "9") (pinfunction "CS2_9") (pintype "input"))
    )
    (net (code "264") (name "~{IRQ}") (class "Default")
      (node (ref "IC17") (pin "4") (pinfunction "IRQ_4") (pintype "input"))
      (node (ref "IC24") (pin "37") (pinfunction "IRQB_37") (pintype "open_collector"))
      (node (ref "IC24") (pin "38") (pinfunction "IRQA_38") (pintype "open_collector"))
      (node (ref "R7") (pin "1") (pinfunction "1_1") (pintype "passive"))
    )
    (net (code "265") (name "~{NMI}") (class "Default")
      (node (ref "IC17") (pin "6") (pinfunction "NMI_6") (pintype "input"))
      (node (ref "IC21") (pin "7") (pinfunction "IRQ_7") (pintype "output"))
      (node (ref "R6") (pin "1") (pinfunction "1_1") (pintype "passive"))
    )
    (net (code "266") (name "~{RST}") (class "Default")
      (node (ref "IC17") (pin "40") (pinfunction "RESET_40") (pintype "input"))
      (node (ref "IC18") (pin "6") (pinfunction "O_6") (pintype "output"))
      (node (ref "IC24") (pin "34") (pinfunction "RESET_34") (pintype "input"))
    )
  )
)
